# soap-disp-mega-16.net
KiCad netlist of a schematic drawn in EasyEDA
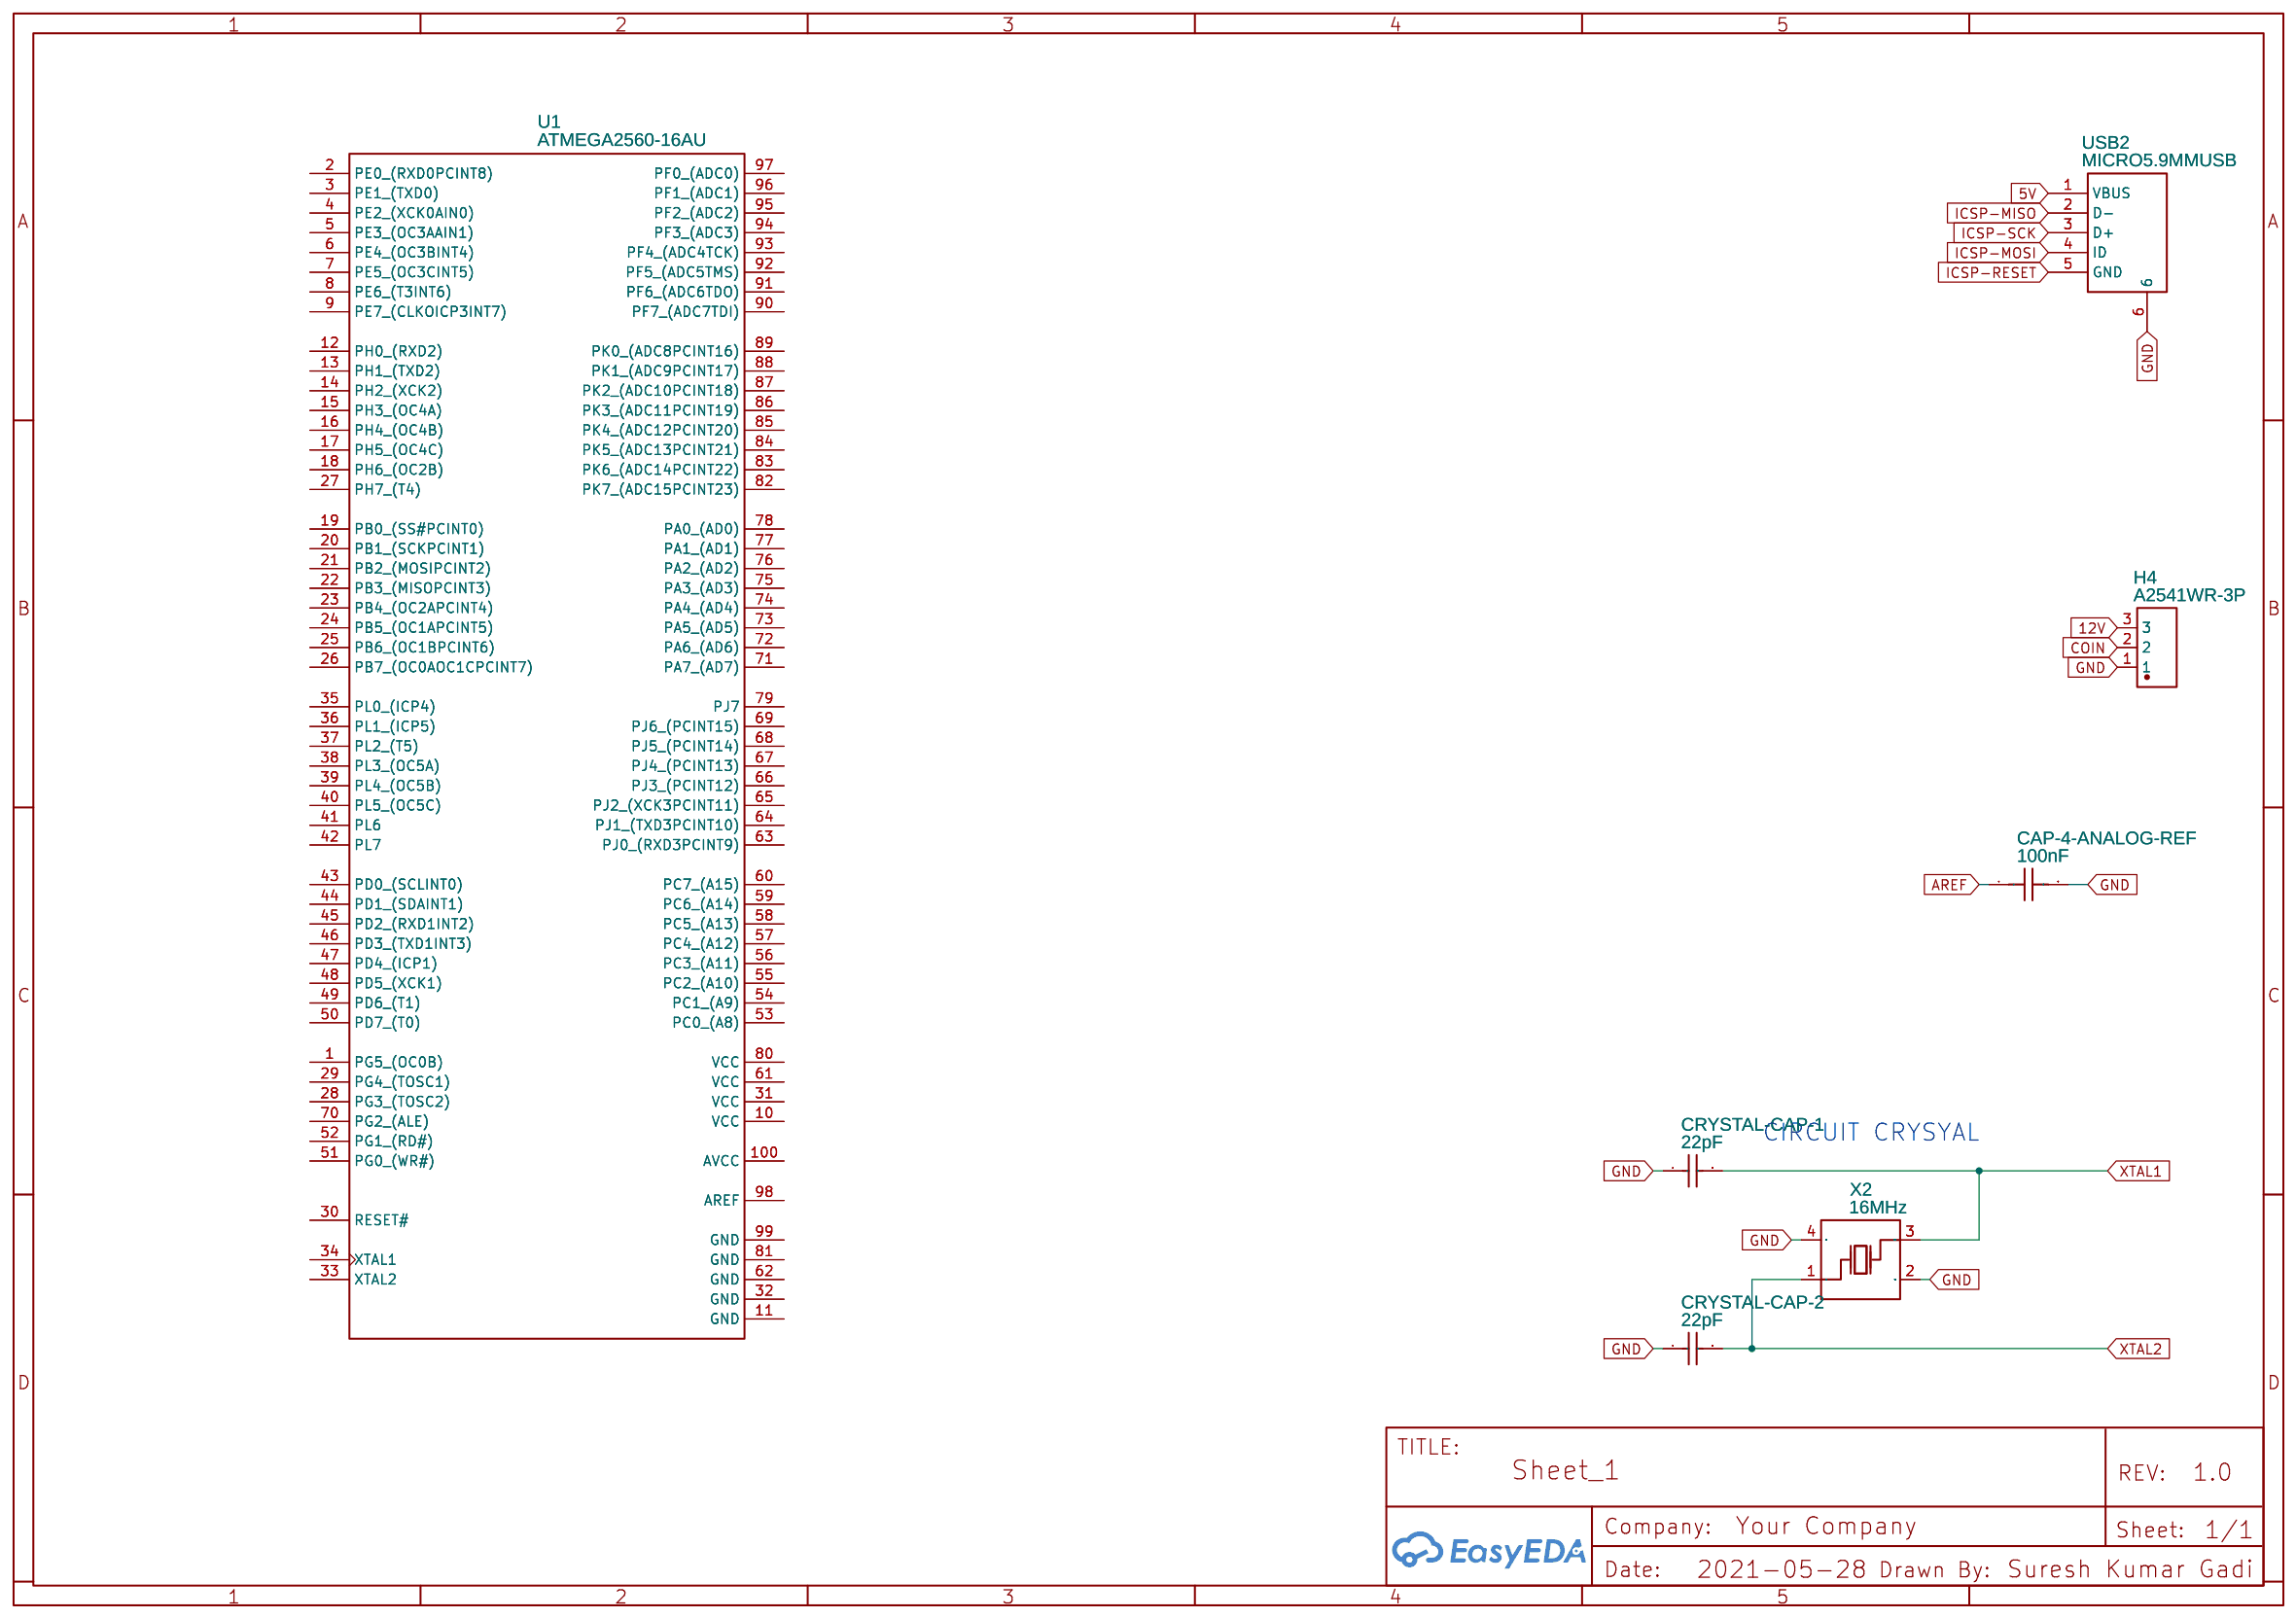
[diagram p0: Computer]
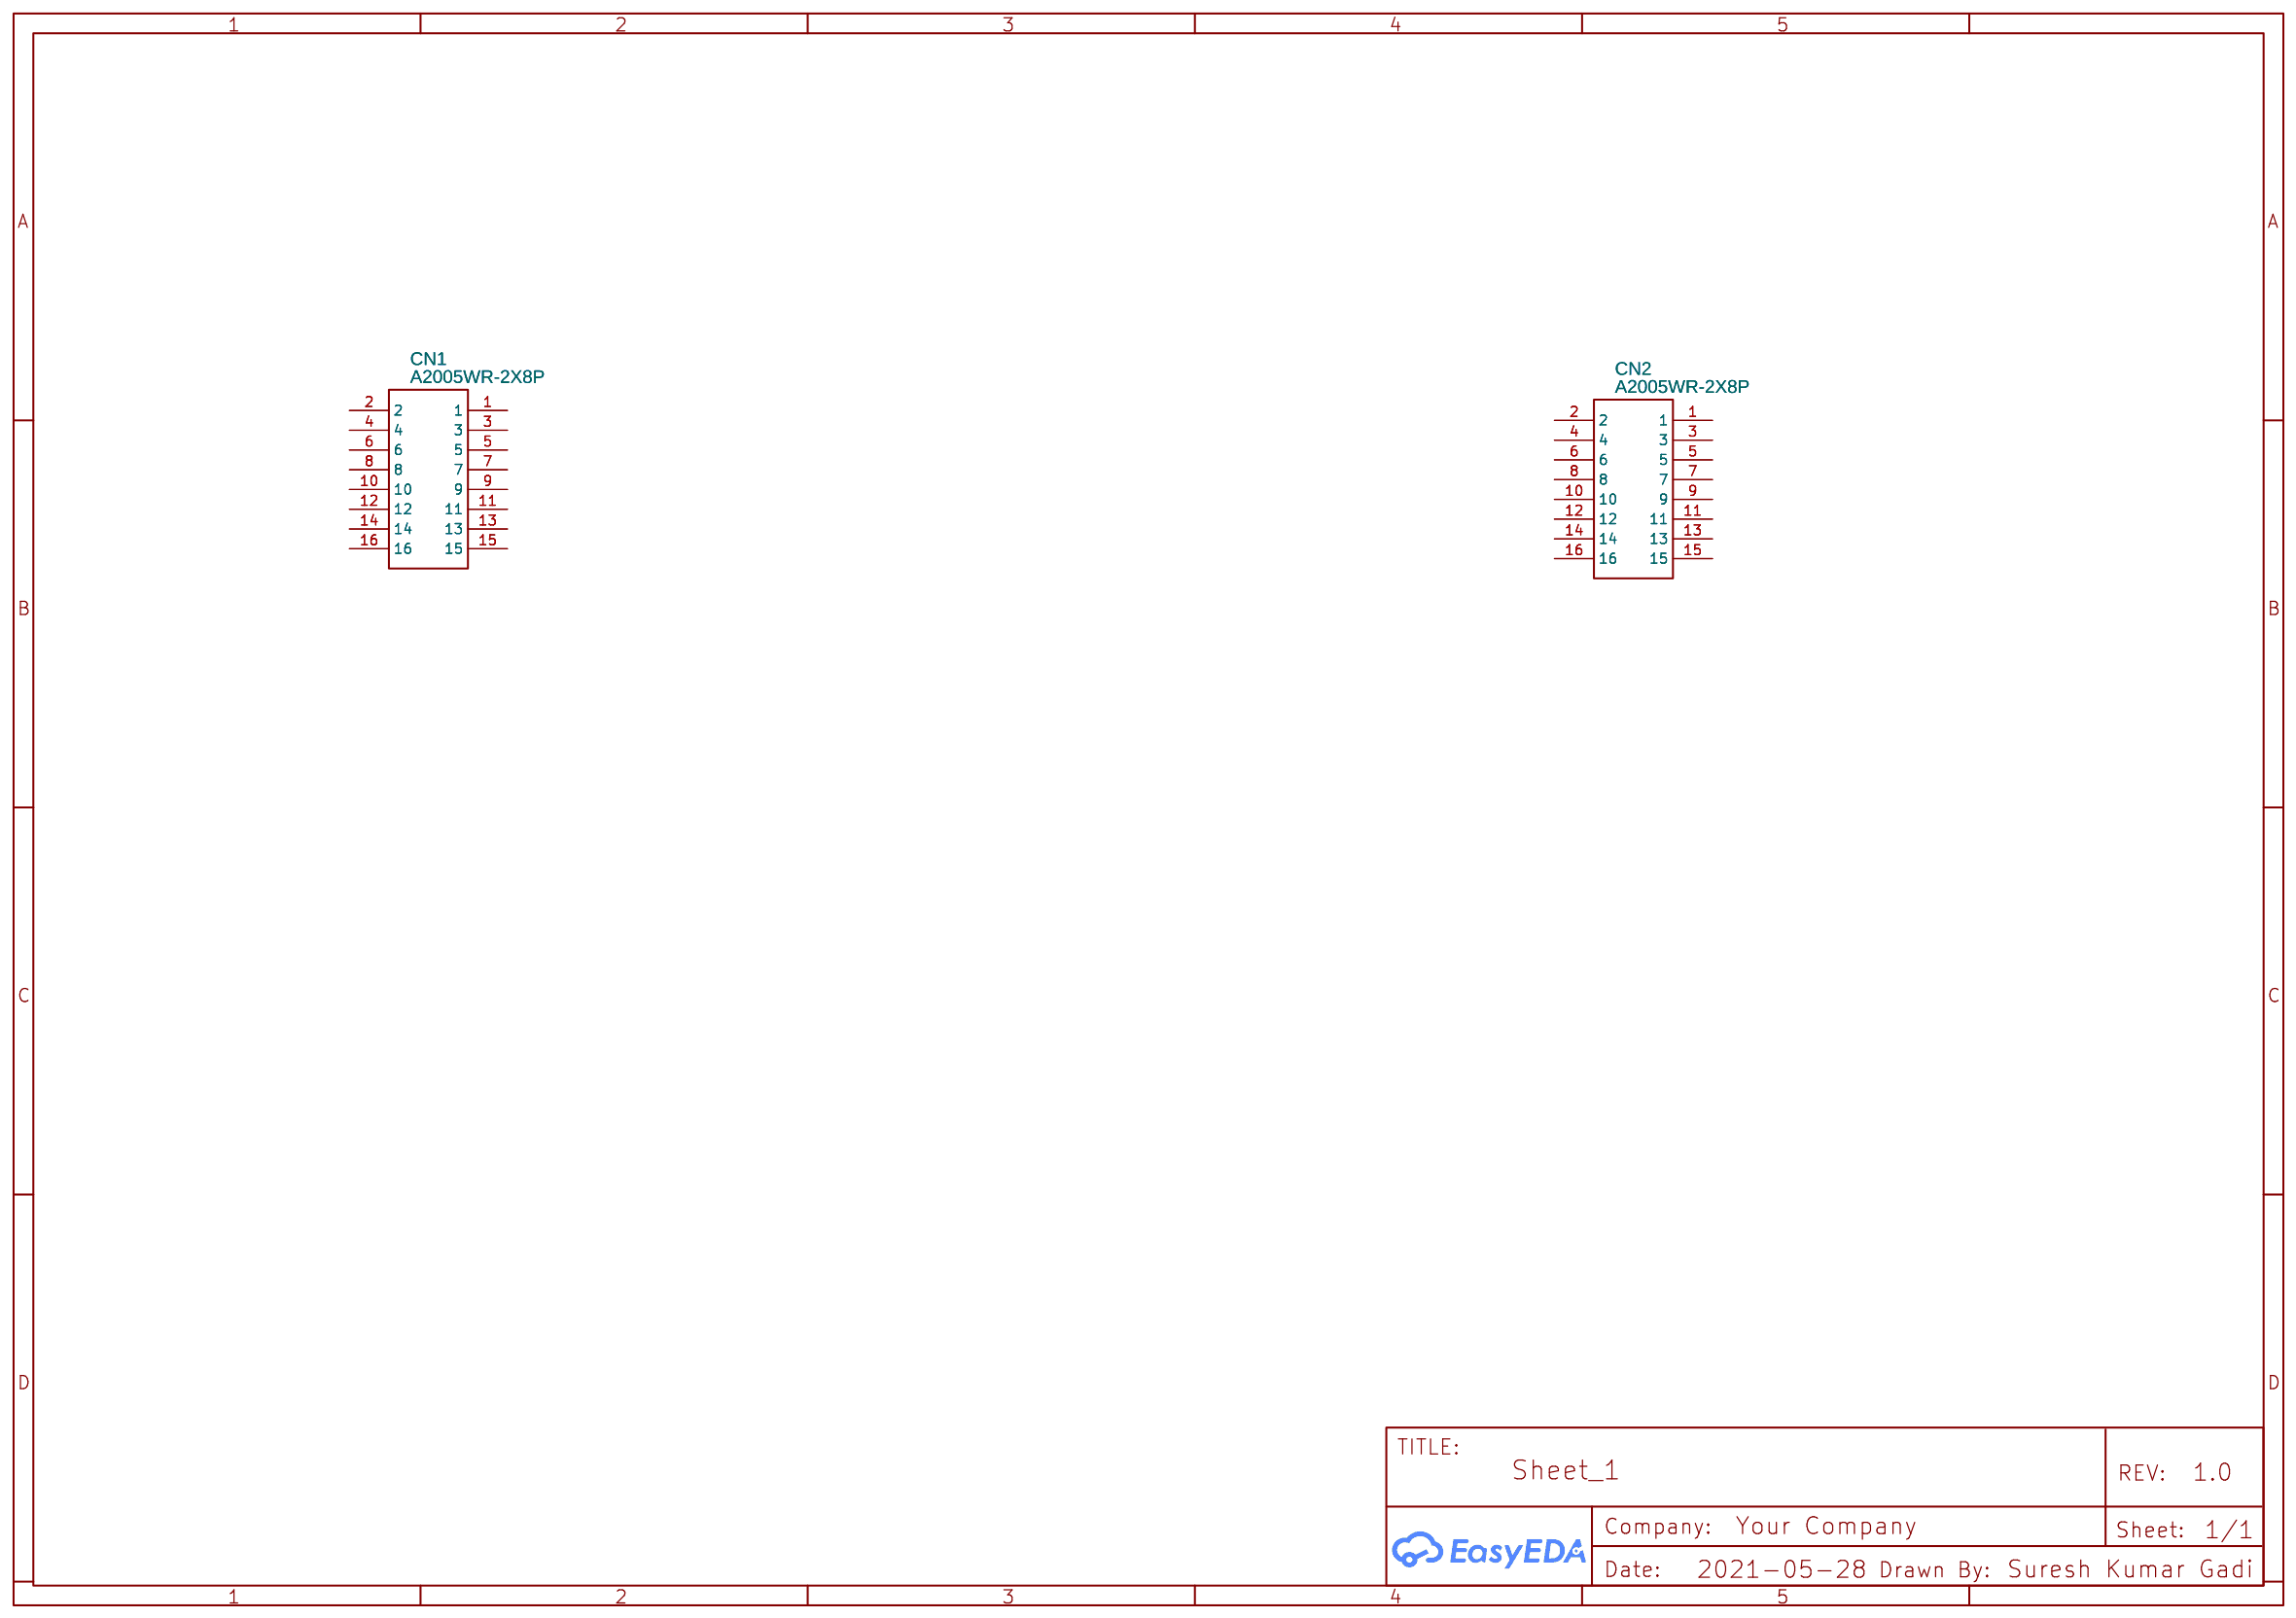
[diagram p1: Connectors]
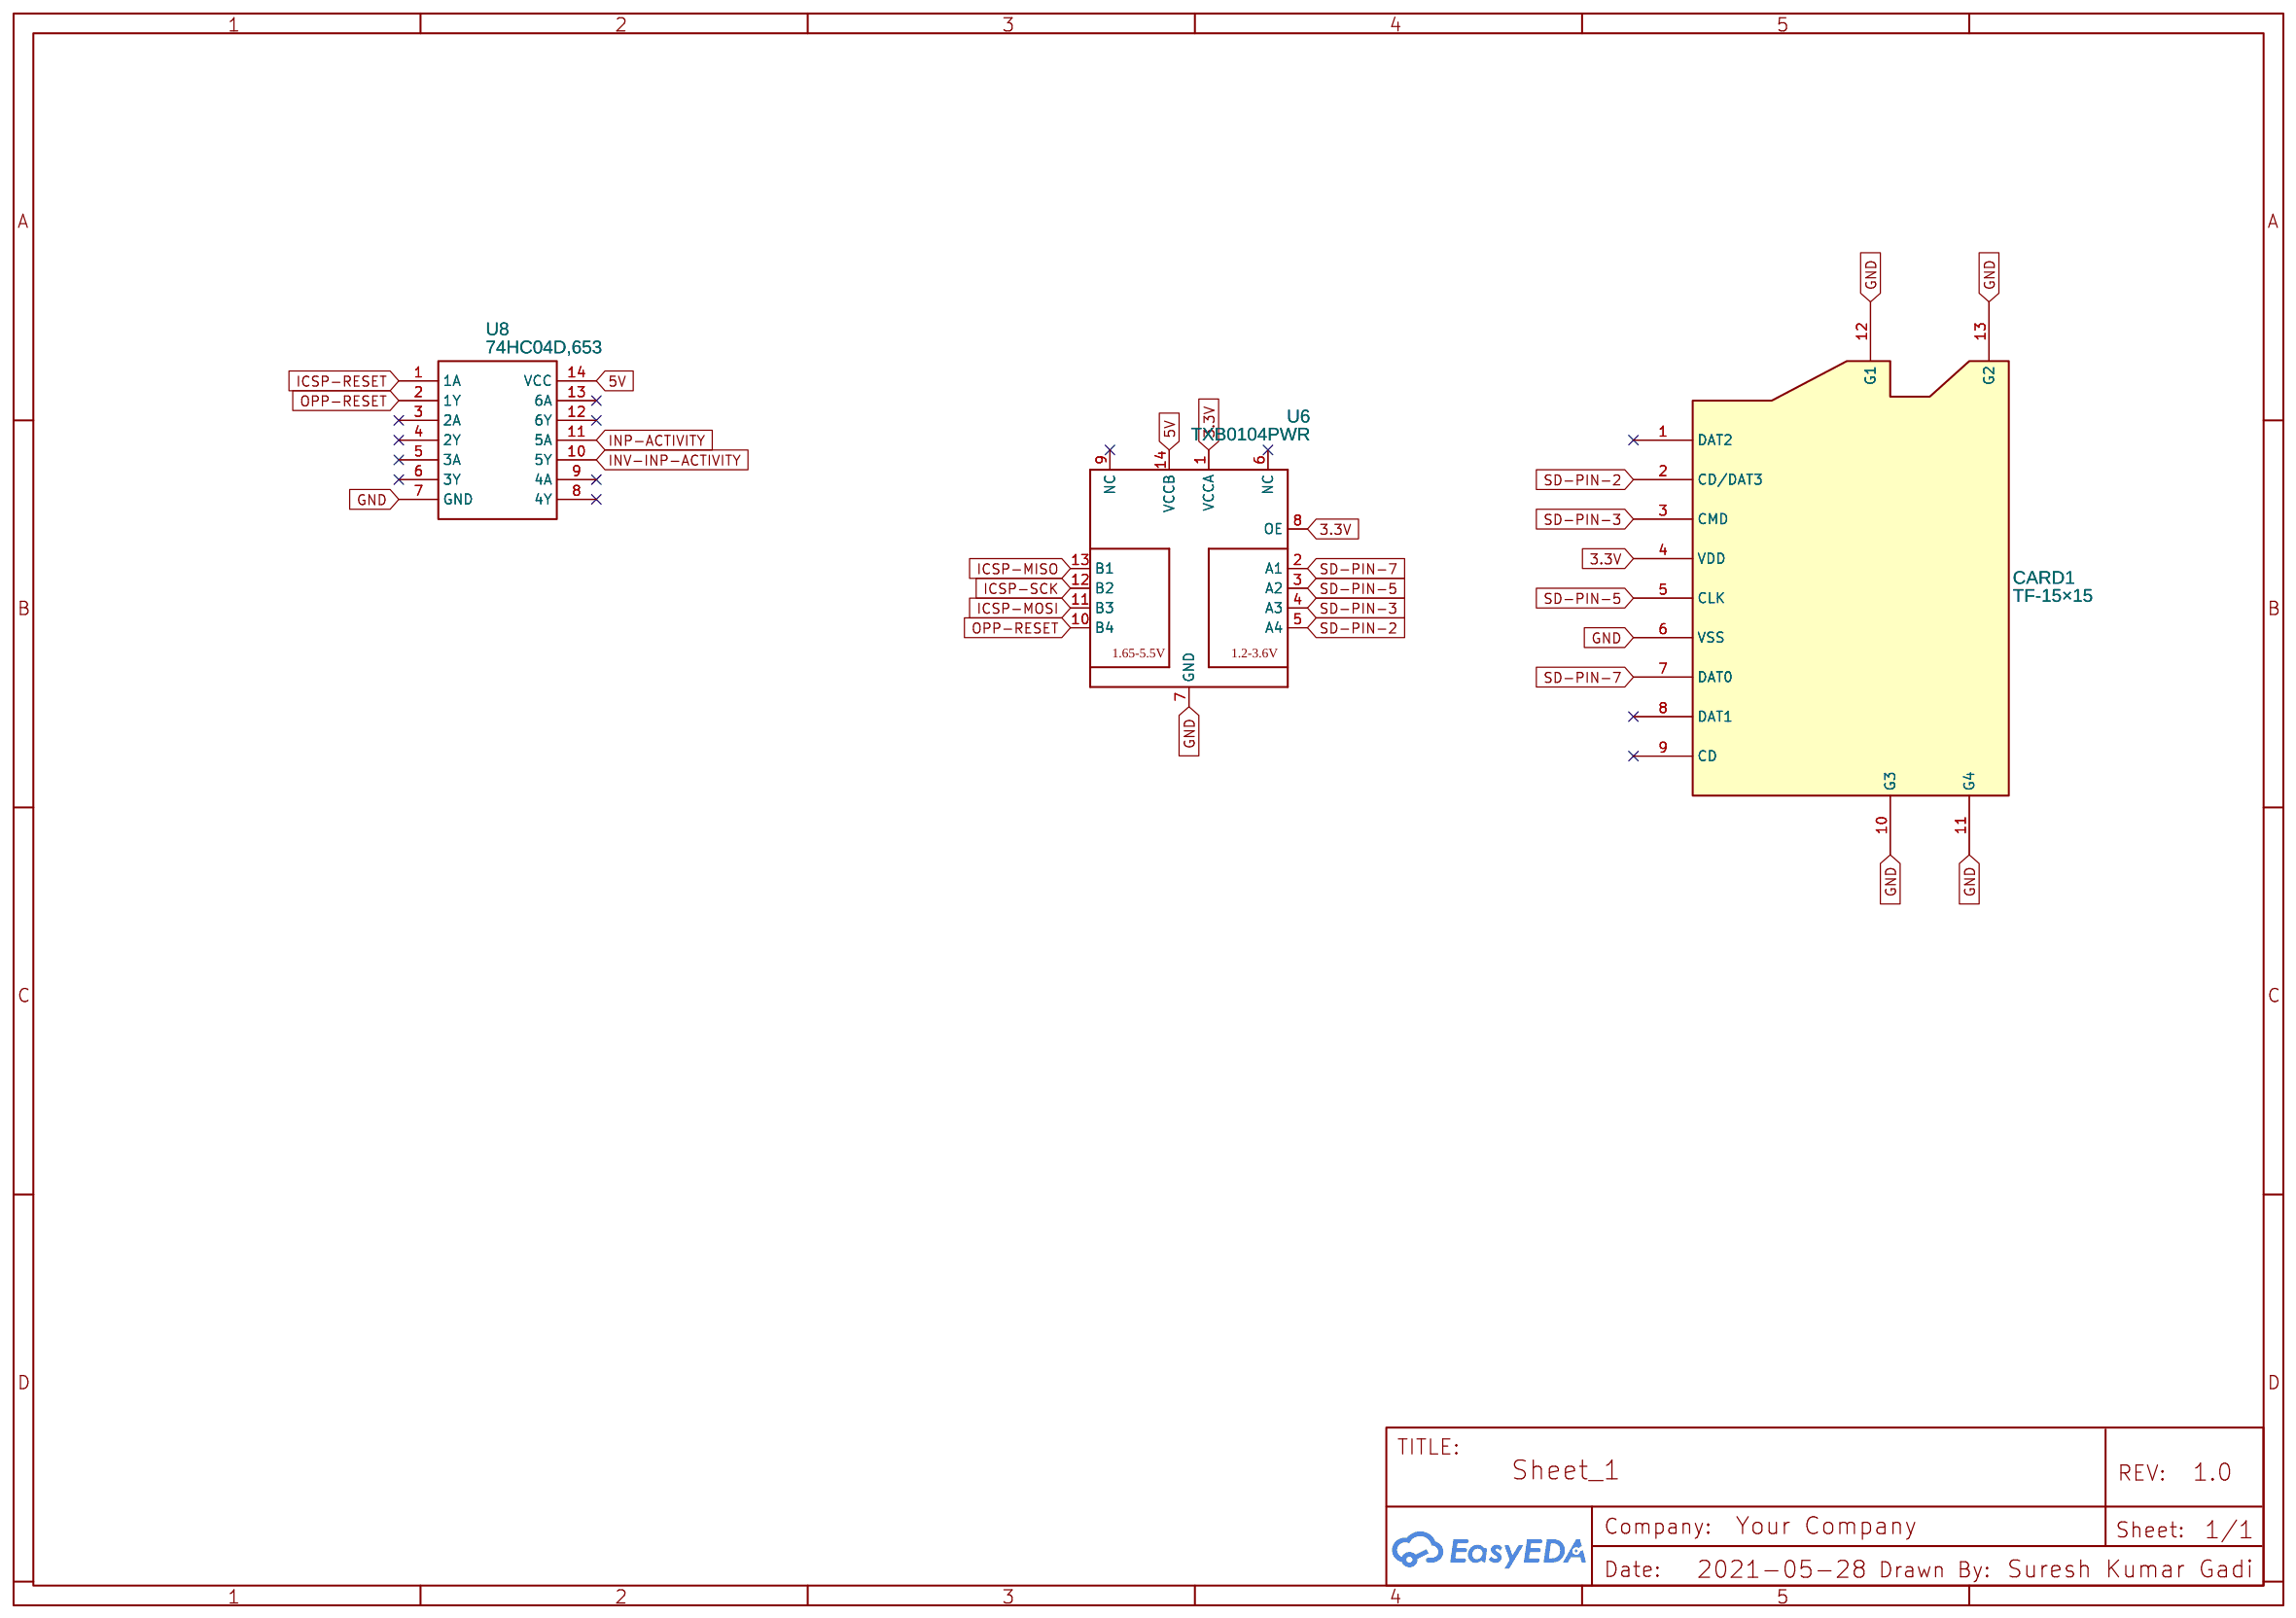
[diagram p2: SD]
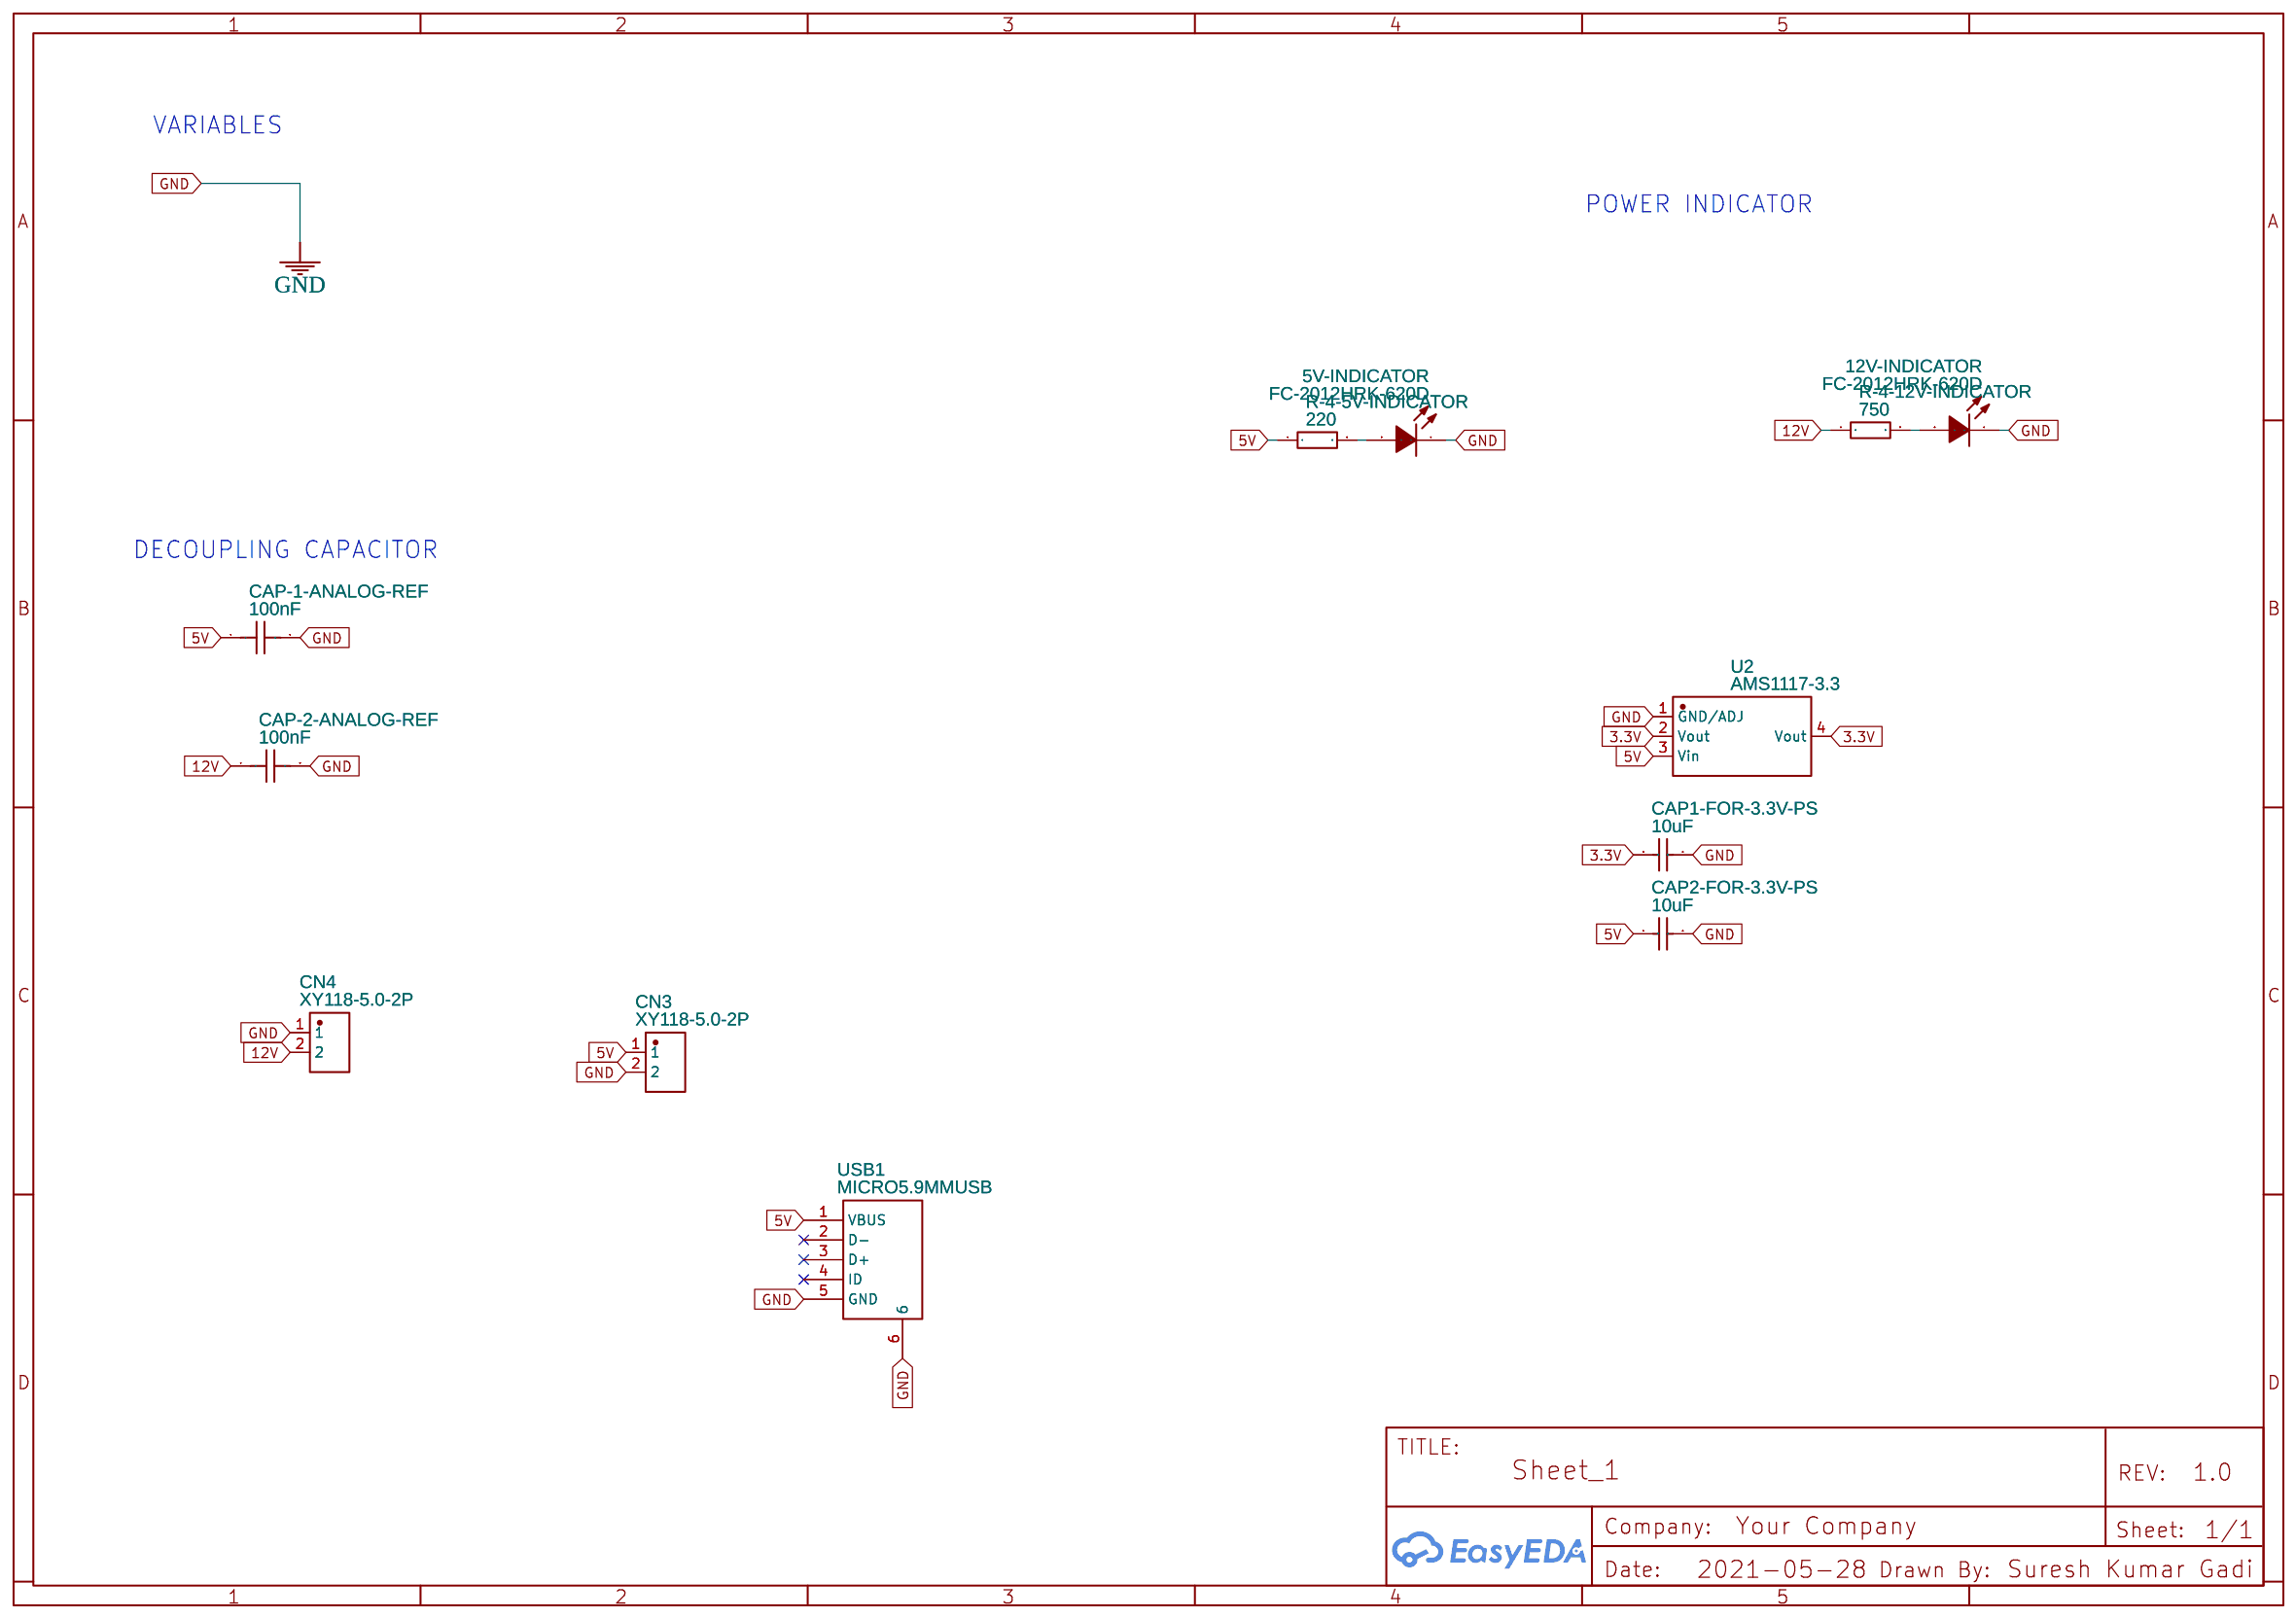
[diagram p3: Power]
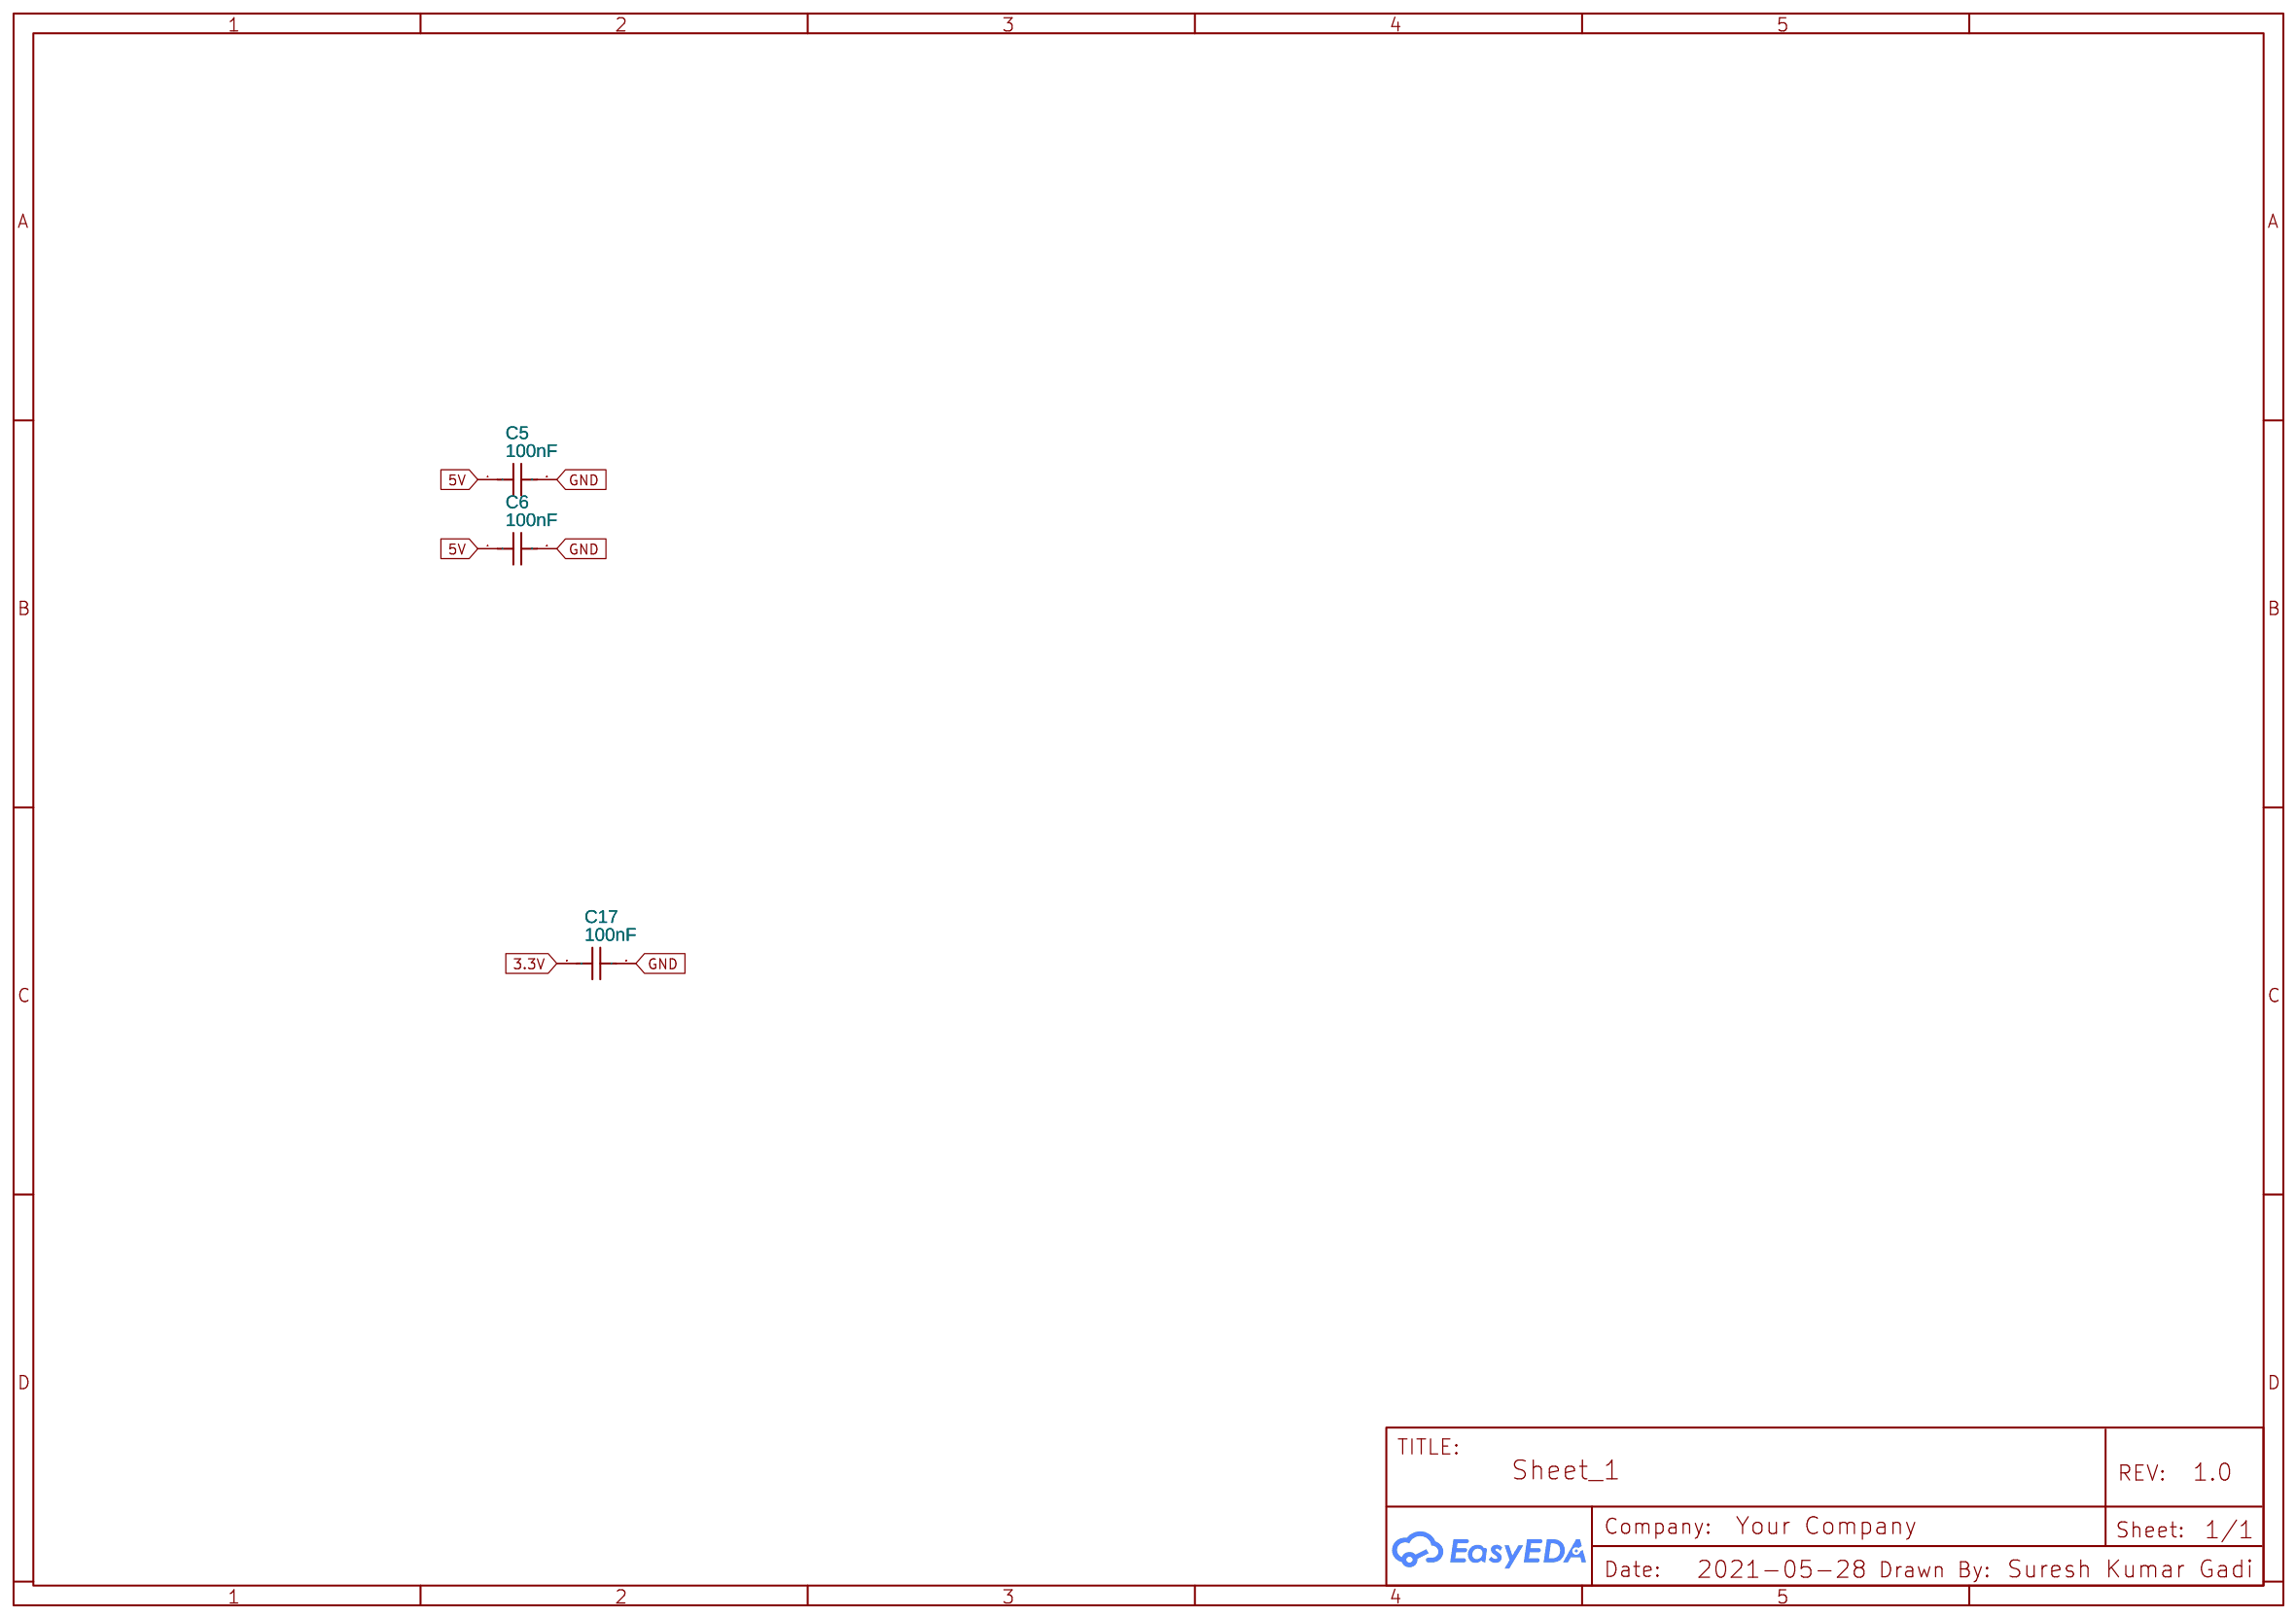
[diagram p4: Capacitors]
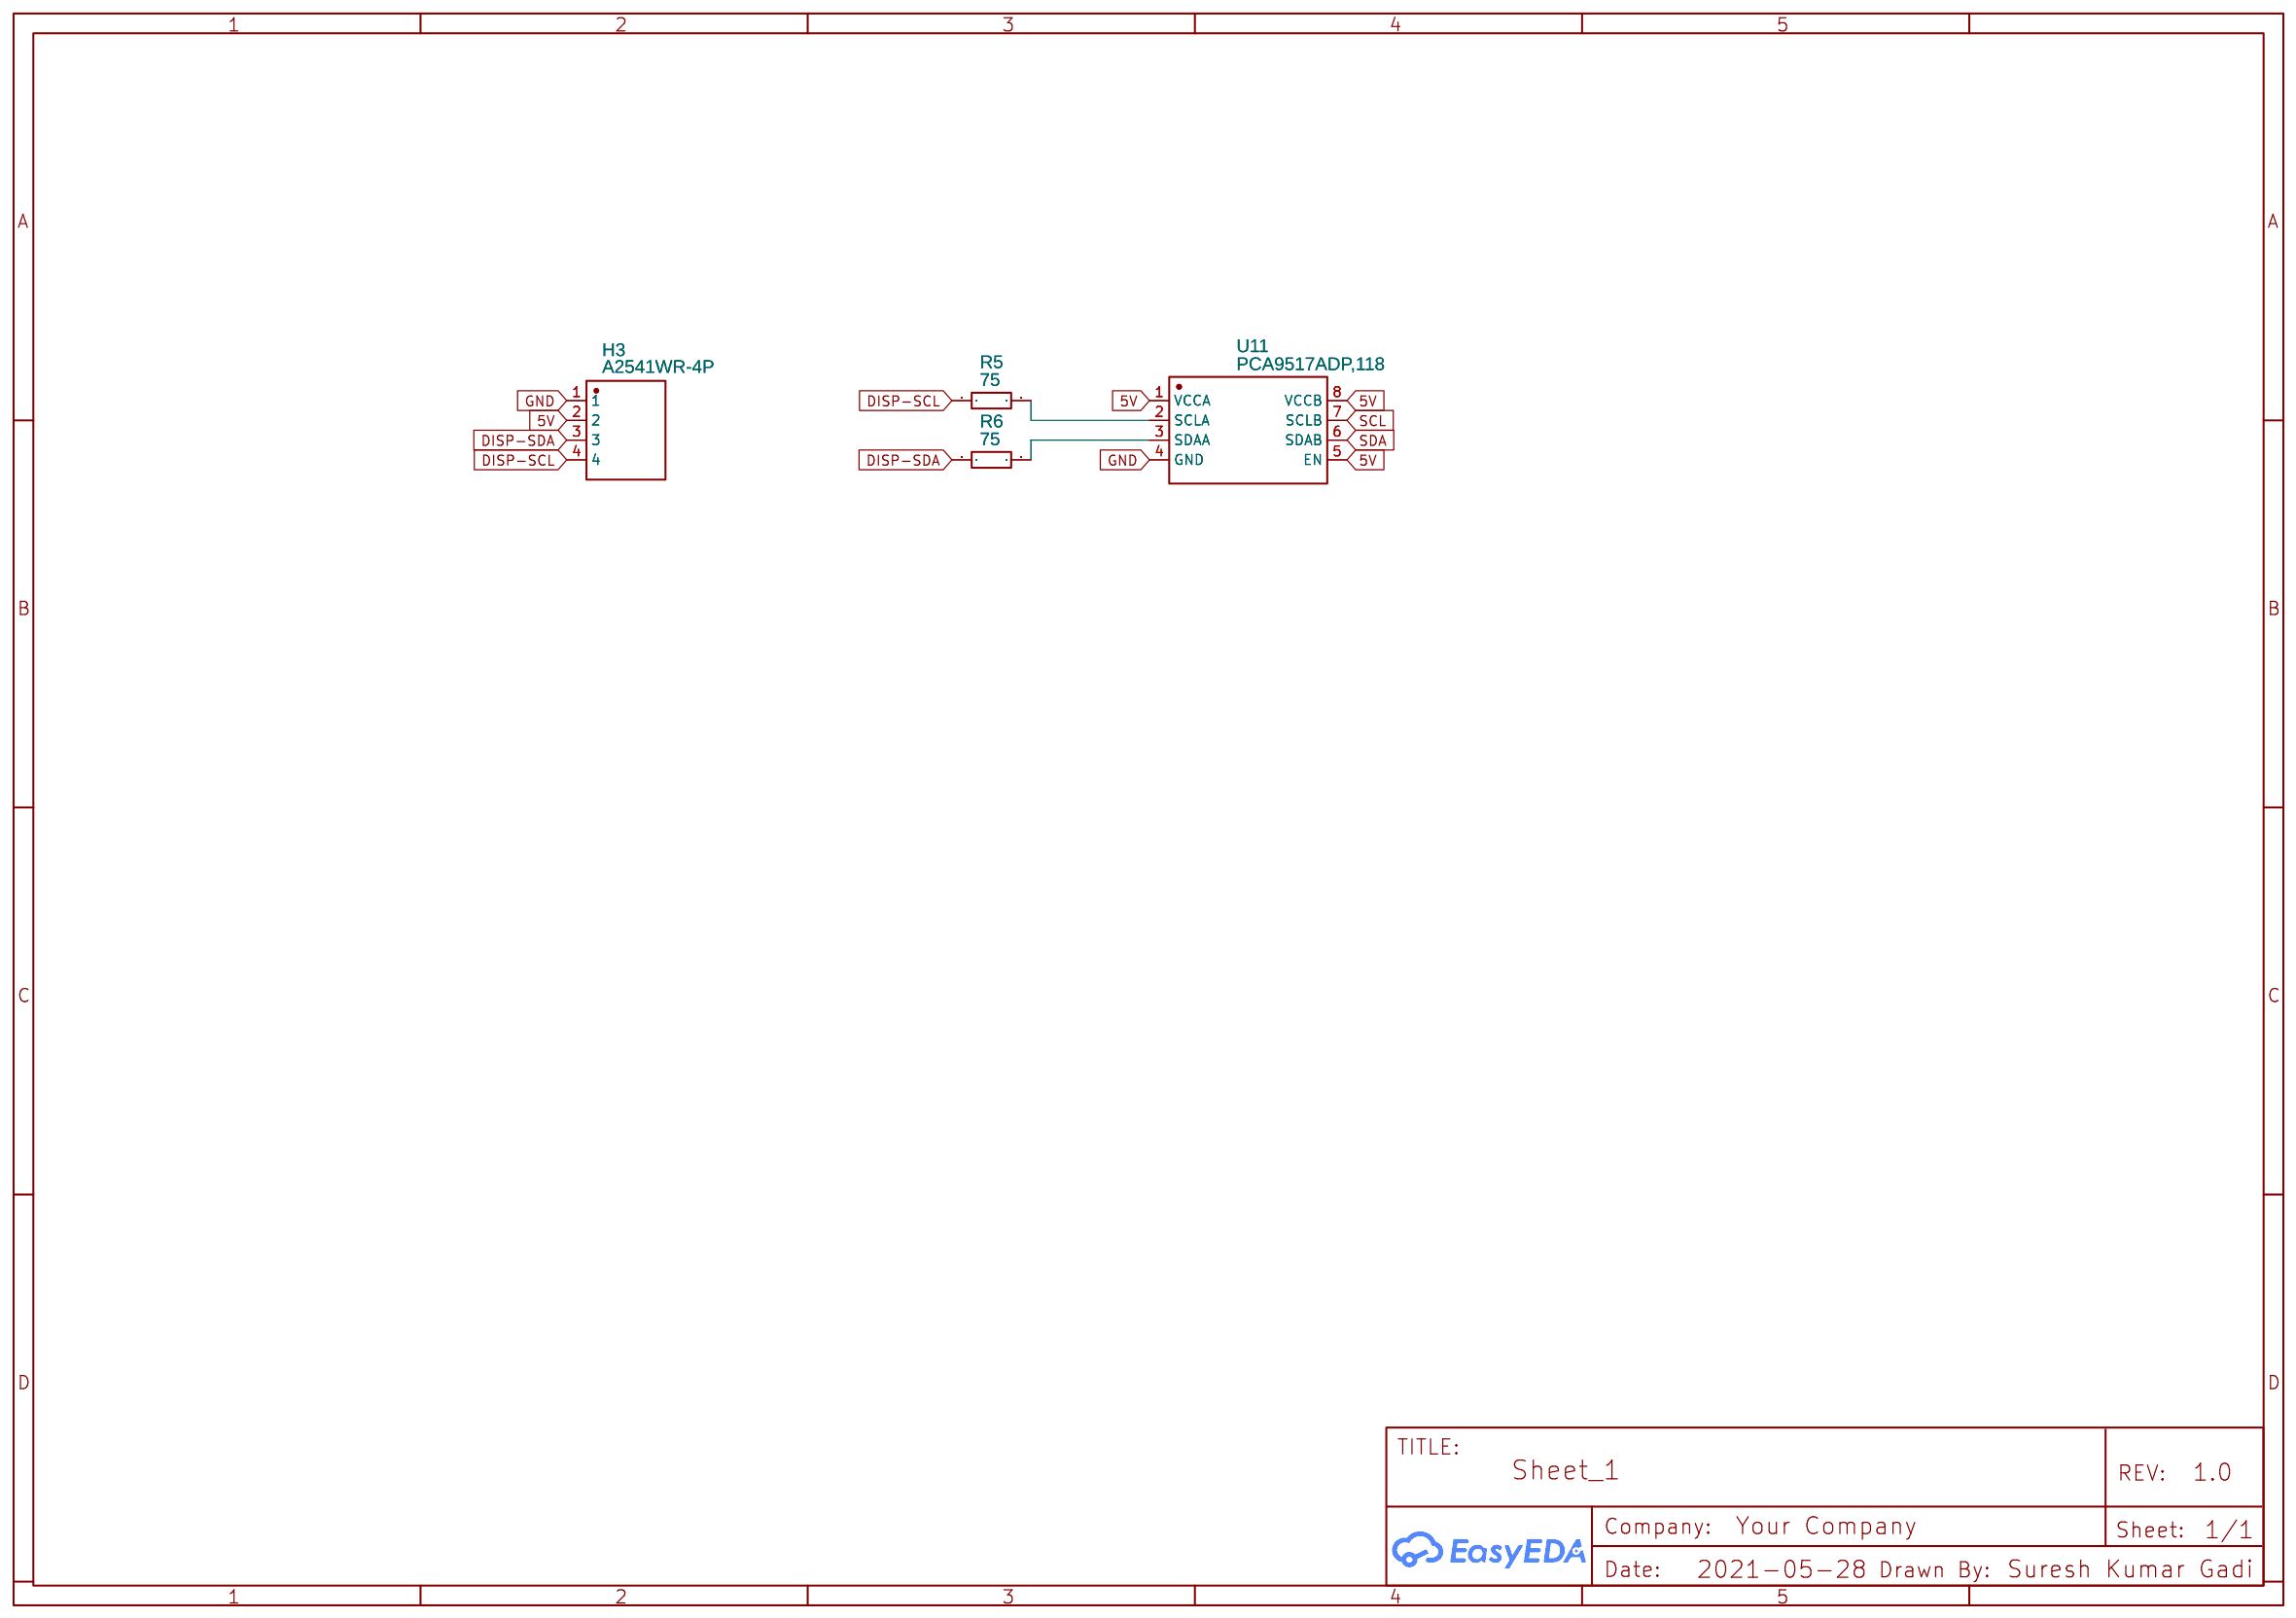
[diagram p5: Display]
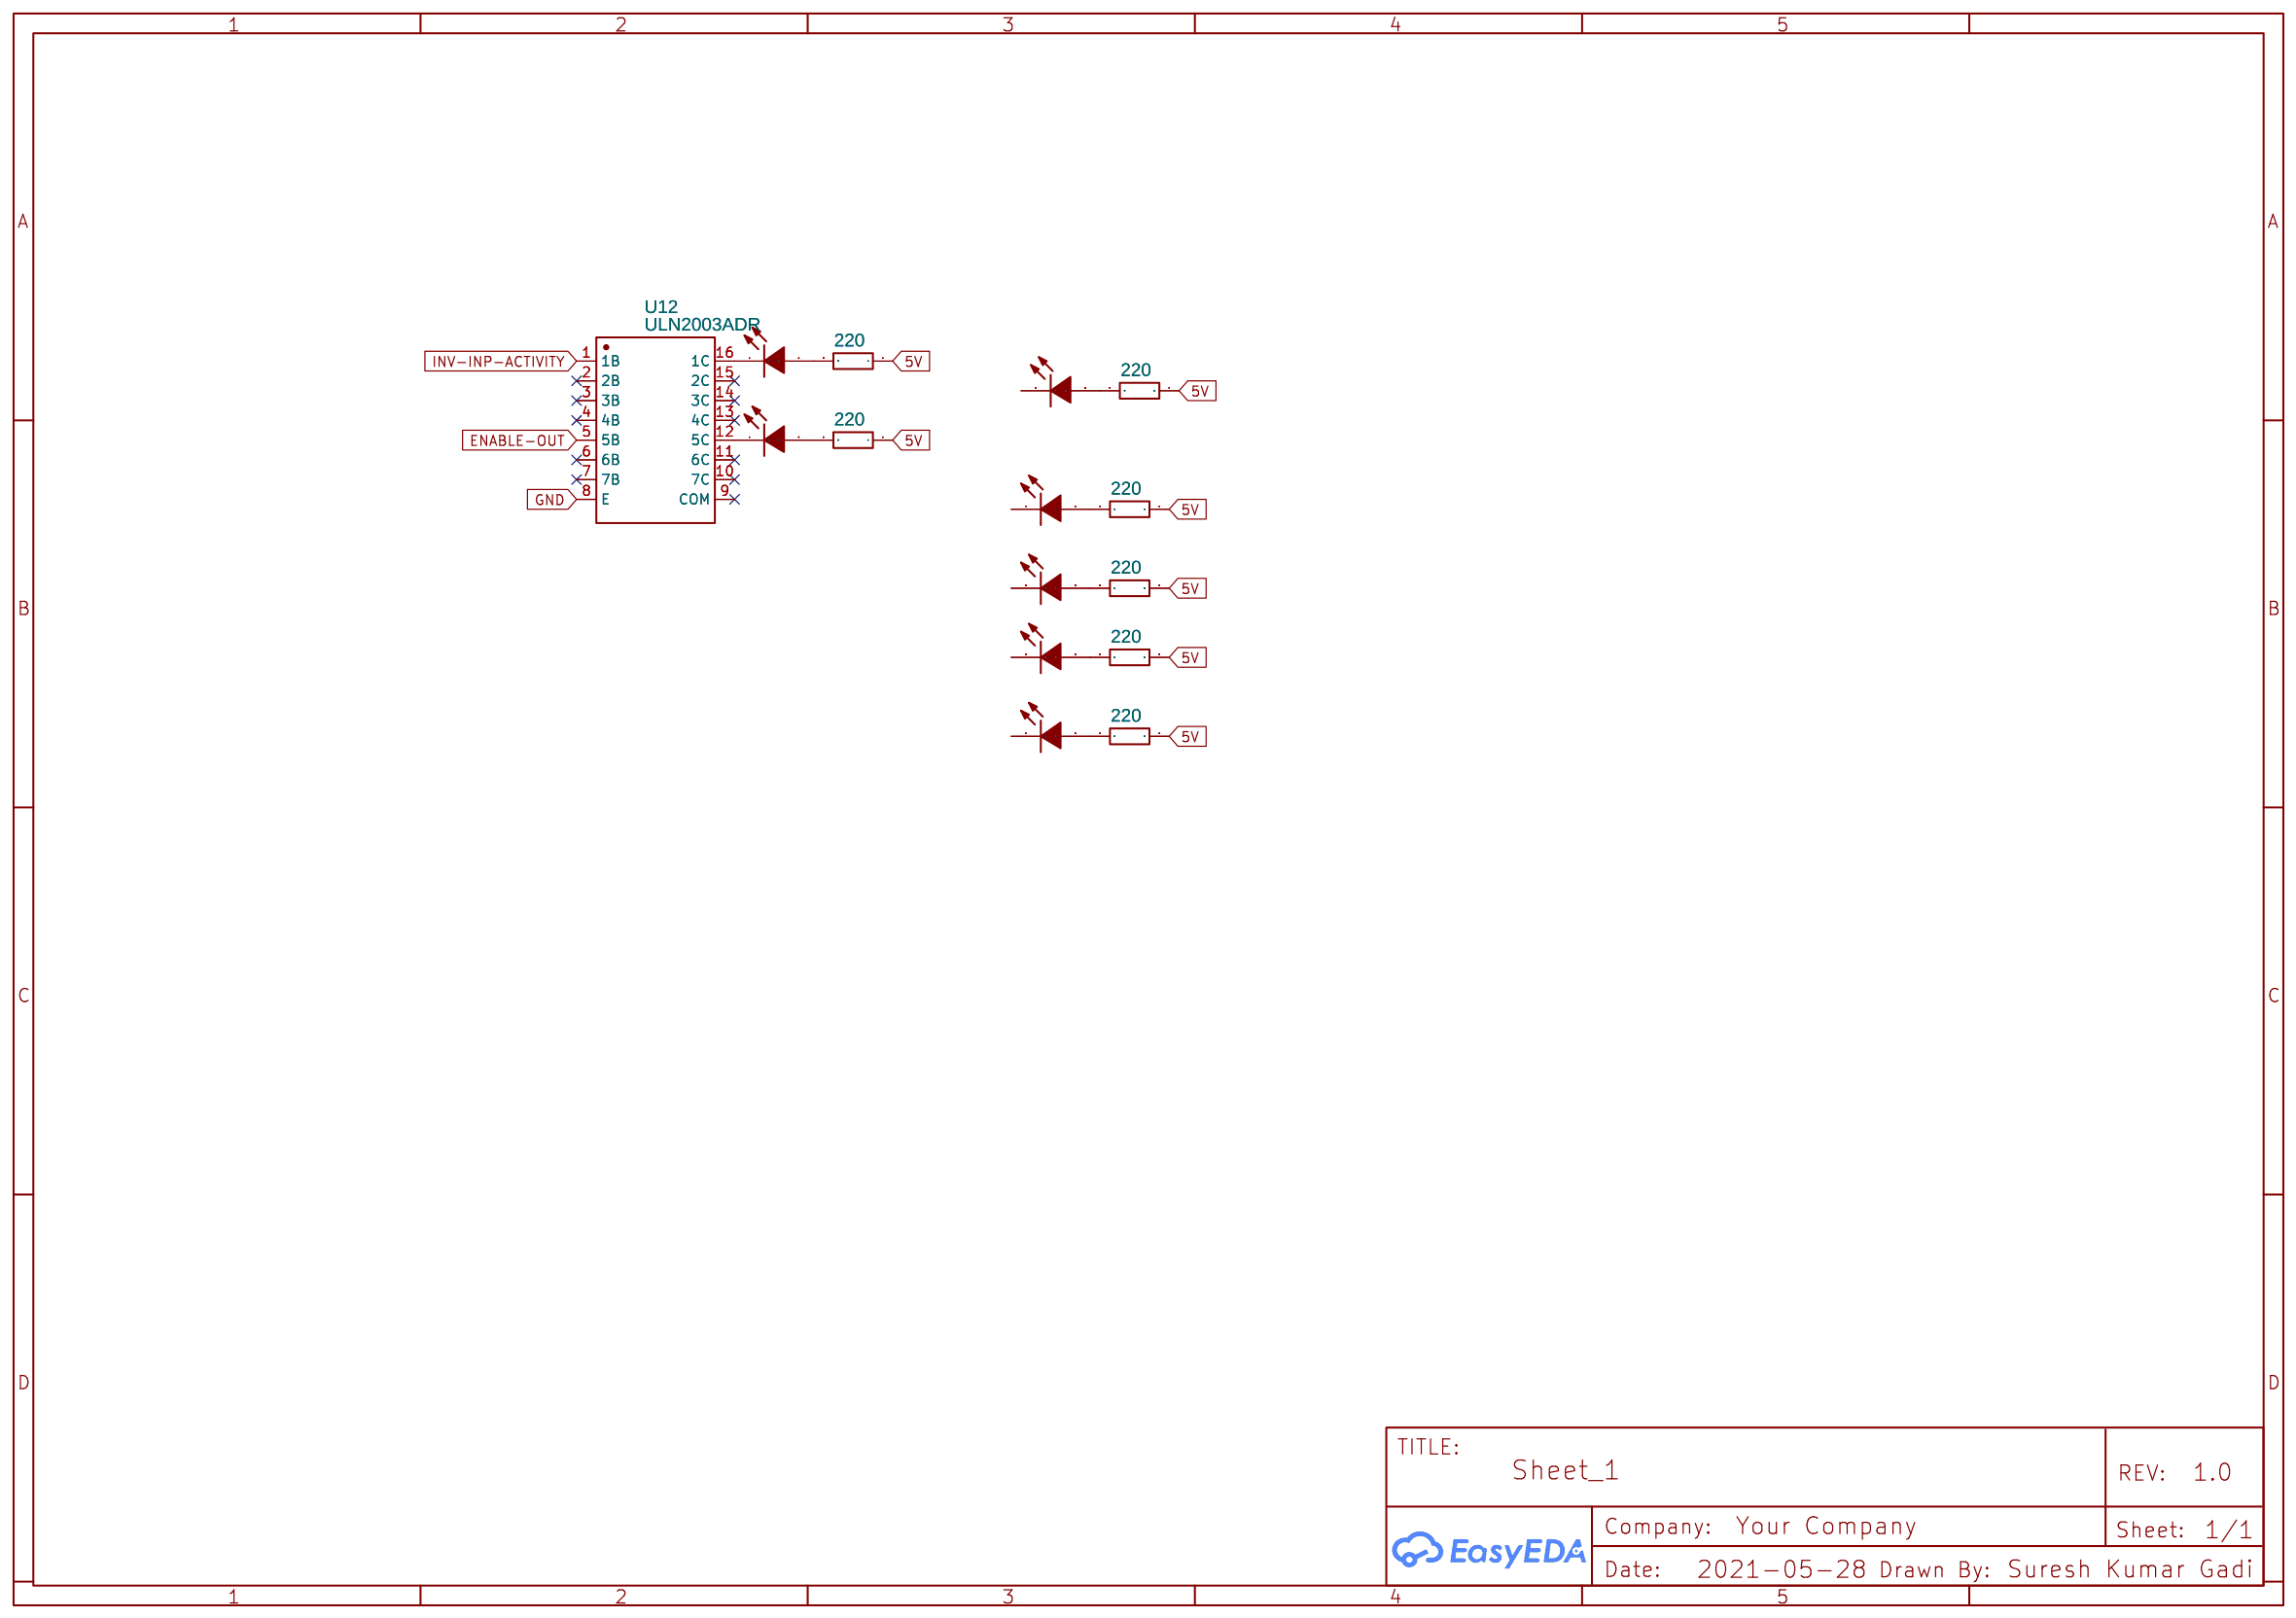
[diagram p6: LEDs]

(export (version "E")
  (design (tool "Eeschema 10.0.6"))
  (components
    (comp (ref "CAP-4-ANALOG-REF")
      (value "100nF")
      (fields
        (field (name "BOM_Manufacturer Part") "CC0603KRX7R9BB104")
        (field (name "BOM_Supplier Part") "C14663")
      )
      (libsource (lib "") (part "CC0603KRX7R9BB104"))
    )
    (comp (ref "CRYSTAL-CAP-1")
      (value "22pF")
      (fields
        (field (name "BOM_Manufacturer Part") "CL21C220JBANNNC")
        (field (name "BOM_Supplier Part") "C1804")
      )
      (libsource (lib "") (part "CL21C220JBANNNC"))
    )
    (comp (ref "CRYSTAL-CAP-2")
      (value "22pF")
      (fields
        (field (name "BOM_Manufacturer Part") "CL21C220JBANNNC")
        (field (name "BOM_Supplier Part") "C1804")
      )
      (libsource (lib "") (part "CL21C220JBANNNC"))
    )
    (comp (ref "H4")
      (value "A2541WR-3P")
      (fields (field (name "BOM_Supplier Part") "C225489"))
      (libsource (lib "") (part "A2541WR-3P"))
    )
    (comp (ref "U1")
      (value "ATMEGA2560-16AU")
      (fields (field (name "BOM_Supplier Part") "C22460"))
      (libsource (lib "") (part "ATMEGA2560-16AU"))
    )
    (comp (ref "USB2")
      (value "MICRO5.9MMUSB")
      (fields
        (field (name "BOM_Manufacturer Part") "MICRO5.9mmusb")
        (field (name "BOM_Supplier Part") "C393940")
      )
      (libsource (lib "") (part "MICRO5.9MMUSB"))
    )
    (comp (ref "X2")
      (value "16MHz")
      (fields
        (field (name "BOM_Manufacturer Part") "X322516MLB4SI")
        (field (name "BOM_Supplier Part") "C13738")
      )
      (libsource (lib "") (part "X322516MLB4SI"))
    )
    (comp (ref "CN1")
      (value "A2005WR-2X8P")
      (fields
        (field (name "BOM_Manufacturer Part") "A2005WR-2x8P")
        (field (name "BOM_Supplier Part") "C225300")
      )
      (libsource (lib "") (part "A2005WR-2X8P"))
    )
    (comp (ref "CN2")
      (value "A2005WR-2X8P")
      (fields
        (field (name "BOM_Manufacturer Part") "A2005WR-2x8P")
        (field (name "BOM_Supplier Part") "C225300")
      )
      (libsource (lib "") (part "A2005WR-2X8P"))
    )
    (comp (ref "CARD1")
      (value "TF-15×15")
      (fields (field (name "BOM_Supplier Part") "C111196"))
      (libsource (lib "") (part "TF-15×15"))
    )
    (comp (ref "U6")
      (value "TXB0104PWR")
      (fields (field (name "BOM_Supplier Part") "C60708"))
      (libsource (lib "") (part "TXB0104PWR"))
    )
    (comp (ref "U8")
      (value "74HC04D,653")
      (fields (field (name "BOM_Supplier Part") "C5590"))
      (libsource (lib "") (part "74HC04D,653"))
    )
    (comp (ref "5V-INDICATOR")
      (value "FC-2012HRK-620D")
      (fields (field (name "BOM_Supplier Part") "C84256"))
      (libsource (lib "") (part "FC-2012HRK-620D_1"))
    )
    (comp (ref "12V-INDICATOR")
      (value "FC-2012HRK-620D")
      (fields (field (name "BOM_Supplier Part") "C84256"))
      (libsource (lib "") (part "FC-2012HRK-620D"))
    )
    (comp (ref "CAP-1-ANALOG-REF")
      (value "100nF")
      (fields
        (field (name "BOM_Manufacturer Part") "CC0603KRX7R9BB104")
        (field (name "BOM_Supplier Part") "C14663")
      )
      (libsource (lib "") (part "CC0603KRX7R9BB104_1"))
    )
    (comp (ref "CAP-2-ANALOG-REF")
      (value "100nF")
      (fields
        (field (name "BOM_Manufacturer Part") "CC0603KRX7R9BB104")
        (field (name "BOM_Supplier Part") "C14663")
      )
      (libsource (lib "") (part "CC0603KRX7R9BB104"))
    )
    (comp (ref "CAP1-FOR-3.3V-PS")
      (value "10uF")
      (fields
        (field (name "BOM_Manufacturer Part") "CL21A106KAYNNNE")
        (field (name "BOM_Supplier Part") "C15850")
      )
      (libsource (lib "") (part "CL21A106KAYNNNE_1"))
    )
    (comp (ref "CAP2-FOR-3.3V-PS")
      (value "10uF")
      (fields
        (field (name "BOM_Manufacturer Part") "CL21A106KAYNNNE")
        (field (name "BOM_Supplier Part") "C15850")
      )
      (libsource (lib "") (part "CL21A106KAYNNNE"))
    )
    (comp (ref "CN3")
      (value "XY118-5.0-2P")
      (fields (field (name "BOM_Supplier Part") "C784922"))
      (libsource (lib "") (part "XY118-5.0-2P"))
    )
    (comp (ref "CN4")
      (value "XY118-5.0-2P")
      (fields (field (name "BOM_Supplier Part") "C784922"))
      (libsource (lib "") (part "XY118-5.0-2P"))
    )
    (comp (ref "R-4-5V-INDICATOR")
      (value "220")
      (fields
        (field (name "BOM_Manufacturer Part") "0805W8F2200T5E")
        (field (name "BOM_Supplier Part") "C17557")
      )
      (libsource (lib "") (part "0805W8F2200T5E"))
    )
    (comp (ref "R-4-12V-INDICATOR")
      (value "750")
      (fields
        (field (name "BOM_Manufacturer Part") "1206W4F7500T5E")
        (field (name "BOM_Supplier Part") "C17985")
      )
      (libsource (lib "") (part "1206W4F7500T5E"))
    )
    (comp (ref "U2")
      (value "AMS1117-3.3")
      (fields (field (name "BOM_Supplier Part") "C6186"))
      (libsource (lib "") (part "AMS1117-3.3"))
    )
    (comp (ref "USB1")
      (value "MICRO5.9MMUSB")
      (fields
        (field (name "BOM_Manufacturer Part") "MICRO5.9mmusb")
        (field (name "BOM_Supplier Part") "C393940")
      )
      (libsource (lib "") (part "MICRO5.9MMUSB"))
    )
    (comp (ref "C5")
      (value "100nF")
      (fields
        (field (name "BOM_Manufacturer Part") "CC0603KRX7R9BB104")
        (field (name "BOM_Supplier Part") "C14663")
      )
      (libsource (lib "") (part "CC0603KRX7R9BB104"))
    )
    (comp (ref "C6")
      (value "100nF")
      (fields
        (field (name "BOM_Manufacturer Part") "CC0603KRX7R9BB104")
        (field (name "BOM_Supplier Part") "C14663")
      )
      (libsource (lib "") (part "CC0603KRX7R9BB104"))
    )
    (comp (ref "C17")
      (value "100nF")
      (fields
        (field (name "BOM_Manufacturer Part") "CC0603KRX7R9BB104")
        (field (name "BOM_Supplier Part") "C14663")
      )
      (libsource (lib "") (part "CC0603KRX7R9BB104"))
    )
    (comp (ref "H3")
      (value "A2541WR-4P")
      (fields (field (name "BOM_Supplier Part") "C225490"))
      (libsource (lib "") (part "A2541WR-4P"))
    )
    (comp (ref "R5")
      (value "75")
      (fields
        (field (name "BOM_Manufacturer Part") "0402WGF750JTCE")
        (field (name "BOM_Supplier Part") "C25133")
      )
      (libsource (lib "") (part "0402WGF750JTCE"))
    )
    (comp (ref "R6")
      (value "75")
      (fields
        (field (name "BOM_Manufacturer Part") "0402WGF750JTCE")
        (field (name "BOM_Supplier Part") "C25133")
      )
      (libsource (lib "") (part "0402WGF750JTCE"))
    )
    (comp (ref "U11")
      (value "PCA9517ADP,118")
      (fields (field (name "BOM_Supplier Part") "C80799"))
      (libsource (lib "") (part "PCA9517ADP,118"))
    )
    (comp (ref "ENAMEOUTINDICATOR1")
      (value "FC-2012HRK-620D")
      (fields (field (name "BOM_Supplier Part") "C84256"))
      (libsource (lib "") (part "FC-2012HRK-620D_1"))
    )
    (comp (ref "ENAMEOUTINDICATOR2")
      (value "FC-2012HRK-620D")
      (fields (field (name "BOM_Supplier Part") "C84256"))
      (libsource (lib "") (part "FC-2012HRK-620D_1"))
    )
    (comp (ref "ENAMEOUTINDICATOR3")
      (value "FC-2012HRK-620D")
      (fields (field (name "BOM_Supplier Part") "C84256"))
      (libsource (lib "") (part "FC-2012HRK-620D_1"))
    )
    (comp (ref "ENAMEOUTINDICATOR4")
      (value "FC-2012HRK-620D")
      (fields (field (name "BOM_Supplier Part") "C84256"))
      (libsource (lib "") (part "FC-2012HRK-620D_1"))
    )
    (comp (ref "INPUTACTIVITYINDICATOR1")
      (value "FC-2012HRK-620D")
      (fields (field (name "BOM_Supplier Part") "C84256"))
      (libsource (lib "") (part "FC-2012HRK-620D"))
    )
    (comp (ref "INPUTACTIVITYINDICATOR2")
      (value "FC-2012HRK-620D")
      (fields (field (name "BOM_Supplier Part") "C84256"))
      (libsource (lib "") (part "FC-2012HRK-620D"))
    )
    (comp (ref "INPUTACTIVITYINDICATOR3")
      (value "FC-2012HRK-620D")
      (fields (field (name "BOM_Supplier Part") "C84256"))
      (libsource (lib "") (part "FC-2012HRK-620D"))
    )
    (comp (ref "R-4-1V-INDICATOR")
      (value "220")
      (fields
        (field (name "BOM_Manufacturer Part") "0805W8F2200T5E")
        (field (name "BOM_Supplier Part") "C17557")
      )
      (libsource (lib "") (part "0805W8F2200T5E"))
    )
    (comp (ref "R-4-2V-INDICATOR")
      (value "220")
      (fields
        (field (name "BOM_Manufacturer Part") "0805W8F2200T5E")
        (field (name "BOM_Supplier Part") "C17557")
      )
      (libsource (lib "") (part "0805W8F2200T5E_3"))
    )
    (comp (ref "R-4-3V-INDICATOR")
      (value "220")
      (fields
        (field (name "BOM_Manufacturer Part") "0805W8F2200T5E")
        (field (name "BOM_Supplier Part") "C17557")
      )
      (libsource (lib "") (part "0805W8F2200T5E_2"))
    )
    (comp (ref "RESFORENAMEOUTINDICATOR1")
      (value "220")
      (fields
        (field (name "BOM_Manufacturer Part") "0805W8F2200T5E")
        (field (name "BOM_Supplier Part") "C17557")
      )
      (libsource (lib "") (part "0805W8F2200T5E_1"))
    )
    (comp (ref "RESFORENAMEOUTINDICATOR2")
      (value "220")
      (fields
        (field (name "BOM_Manufacturer Part") "0805W8F2200T5E")
        (field (name "BOM_Supplier Part") "C17557")
      )
      (libsource (lib "") (part "0805W8F2200T5E_1"))
    )
    (comp (ref "RESFORENAMEOUTINDICATOR3")
      (value "220")
      (fields
        (field (name "BOM_Manufacturer Part") "0805W8F2200T5E")
        (field (name "BOM_Supplier Part") "C17557")
      )
      (libsource (lib "") (part "0805W8F2200T5E_1"))
    )
    (comp (ref "RESFORENAMEOUTINDICATOR4")
      (value "220")
      (fields
        (field (name "BOM_Manufacturer Part") "0805W8F2200T5E")
        (field (name "BOM_Supplier Part") "C17557")
      )
      (libsource (lib "") (part "0805W8F2200T5E_1"))
    )
    (comp (ref "U12")
      (value "ULN2003ADR")
      (fields (field (name "BOM_Supplier Part") "C7512"))
      (libsource (lib "") (part "ULN2003ADR"))
    )
  )
  (nets
    (net (code "1") (name "3.3V") (class "Default")
      (node (ref "C17") (pin "1") (pinfunction "1_1") (pintype "unspecified"))
      (node (ref "CAP1-FOR-3.3V-PS") (pin "1") (pinfunction "1_1") (pintype "input"))
      (node (ref "CARD1") (pin "4") (pinfunction "VDD_4") (pintype "input"))
      (node (ref "U2") (pin "2") (pinfunction "Vout_2") (pintype "unspecified"))
      (node (ref "U2") (pin "4") (pinfunction "Vout_4") (pintype "unspecified"))
      (node (ref "U6") (pin "1") (pinfunction "VCCA_1") (pintype "unspecified"))
      (node (ref "U6") (pin "8") (pinfunction "OE_8") (pintype "unspecified"))
    )
    (net (code "2") (name "5V") (class "Default")
      (node (ref "C5") (pin "1") (pinfunction "1_1") (pintype "unspecified"))
      (node (ref "C6") (pin "1") (pinfunction "1_1") (pintype "unspecified"))
      (node (ref "CAP-1-ANALOG-REF") (pin "1") (pinfunction "1_1") (pintype "unspecified"))
      (node (ref "CAP2-FOR-3.3V-PS") (pin "1") (pinfunction "1_1") (pintype "input"))
      (node (ref "CN3") (pin "1") (pinfunction "1_1") (pintype "unspecified"))
      (node (ref "H3") (pin "2") (pinfunction "2_2") (pintype "unspecified"))
      (node (ref "R-4-1V-INDICATOR") (pin "1") (pinfunction "1_1") (pintype "input"))
      (node (ref "R-4-2V-INDICATOR") (pin "1") (pinfunction "1_1") (pintype "input"))
      (node (ref "R-4-3V-INDICATOR") (pin "1") (pinfunction "1_1") (pintype "input"))
      (node (ref "R-4-5V-INDICATOR") (pin "1") (pinfunction "1_1") (pintype "input"))
      (node (ref "RESFORENAMEOUTINDICATOR1") (pin "1") (pinfunction "1_1") (pintype "input"))
      (node (ref "RESFORENAMEOUTINDICATOR2") (pin "1") (pinfunction "1_1") (pintype "input"))
      (node (ref "RESFORENAMEOUTINDICATOR3") (pin "1") (pinfunction "1_1") (pintype "input"))
      (node (ref "RESFORENAMEOUTINDICATOR4") (pin "1") (pinfunction "1_1") (pintype "input"))
      (node (ref "U11") (pin "1") (pinfunction "VCCA_1") (pintype "unspecified"))
      (node (ref "U11") (pin "5") (pinfunction "EN_5") (pintype "unspecified"))
      (node (ref "U11") (pin "8") (pinfunction "VCCB_8") (pintype "unspecified"))
      (node (ref "U2") (pin "3") (pinfunction "Vin_3") (pintype "unspecified"))
      (node (ref "U6") (pin "14") (pinfunction "VCCB_14") (pintype "unspecified"))
      (node (ref "U8") (pin "14") (pinfunction "VCC_14") (pintype "unspecified"))
      (node (ref "USB1") (pin "1") (pinfunction "VBUS_1") (pintype "unspecified"))
      (node (ref "USB2") (pin "1") (pinfunction "VBUS_1") (pintype "unspecified"))
    )
    (net (code "3") (name "12V") (class "Default")
      (node (ref "CAP-2-ANALOG-REF") (pin "1") (pinfunction "1_1") (pintype "unspecified"))
      (node (ref "CN4") (pin "2") (pinfunction "2_2") (pintype "unspecified"))
      (node (ref "H4") (pin "3") (pinfunction "3_3") (pintype "unspecified"))
      (node (ref "R-4-12V-INDICATOR") (pin "1") (pinfunction "1_1") (pintype "input"))
    )
    (net (code "4") (name "AREF") (class "Default")
      (node (ref "CAP-4-ANALOG-REF") (pin "1") (pinfunction "1_1") (pintype "unspecified"))
    )
    (net (code "5") (name "COIN") (class "Default")
      (node (ref "H4") (pin "2") (pinfunction "2_2") (pintype "unspecified"))
    )
    (net (code "6") (name "DISP-SCL") (class "Default")
      (node (ref "H3") (pin "4") (pinfunction "4_4") (pintype "unspecified"))
      (node (ref "R5") (pin "1") (pinfunction "1_1") (pintype "input"))
    )
    (net (code "7") (name "DISP-SDA") (class "Default")
      (node (ref "H3") (pin "3") (pinfunction "3_3") (pintype "unspecified"))
      (node (ref "R6") (pin "1") (pinfunction "1_1") (pintype "input"))
    )
    (net (code "8") (name "ENABLE-OUT") (class "Default")
      (node (ref "U12") (pin "5") (pinfunction "5B_5") (pintype "unspecified"))
    )
    (net (code "9") (name "GND") (class "Default")
      (node (ref "12V-INDICATOR") (pin "1") (pinfunction "-_1") (pintype "unspecified"))
      (node (ref "5V-INDICATOR") (pin "1") (pinfunction "-_1") (pintype "unspecified"))
      (node (ref "C17") (pin "2") (pinfunction "2_2") (pintype "unspecified"))
      (node (ref "C5") (pin "2") (pinfunction "2_2") (pintype "unspecified"))
      (node (ref "C6") (pin "2") (pinfunction "2_2") (pintype "unspecified"))
      (node (ref "CAP-1-ANALOG-REF") (pin "2") (pinfunction "2_2") (pintype "unspecified"))
      (node (ref "CAP-2-ANALOG-REF") (pin "2") (pinfunction "2_2") (pintype "unspecified"))
      (node (ref "CAP-4-ANALOG-REF") (pin "2") (pinfunction "2_2") (pintype "unspecified"))
      (node (ref "CAP1-FOR-3.3V-PS") (pin "2") (pinfunction "2_2") (pintype "input"))
      (node (ref "CAP2-FOR-3.3V-PS") (pin "2") (pinfunction "2_2") (pintype "input"))
      (node (ref "CARD1") (pin "10") (pinfunction "G3_10") (pintype "input"))
      (node (ref "CARD1") (pin "11") (pinfunction "G4_11") (pintype "input"))
      (node (ref "CARD1") (pin "12") (pinfunction "G1_12") (pintype "input"))
      (node (ref "CARD1") (pin "13") (pinfunction "G2_13") (pintype "input"))
      (node (ref "CARD1") (pin "6") (pinfunction "VSS_6") (pintype "input"))
      (node (ref "CN3") (pin "2") (pinfunction "2_2") (pintype "unspecified"))
      (node (ref "CN4") (pin "1") (pinfunction "1_1") (pintype "unspecified"))
      (node (ref "CRYSTAL-CAP-1") (pin "1") (pinfunction "1_1") (pintype "input"))
      (node (ref "CRYSTAL-CAP-2") (pin "1") (pinfunction "1_1") (pintype "input"))
      (node (ref "H3") (pin "1") (pinfunction "1_1") (pintype "unspecified"))
      (node (ref "H4") (pin "1") (pinfunction "1_1") (pintype "unspecified"))
      (node (ref "U11") (pin "4") (pinfunction "GND_4") (pintype "unspecified"))
      (node (ref "U12") (pin "8") (pinfunction "E_8") (pintype "unspecified"))
      (node (ref "U2") (pin "1") (pinfunction "GND/ADJ_1") (pintype "unspecified"))
      (node (ref "U6") (pin "7") (pinfunction "GND_7") (pintype "unspecified"))
      (node (ref "U8") (pin "7") (pinfunction "GND_7") (pintype "unspecified"))
      (node (ref "USB1") (pin "5") (pinfunction "GND_5") (pintype "unspecified"))
      (node (ref "USB1") (pin "6") (pinfunction "6_6") (pintype "unspecified"))
      (node (ref "USB2") (pin "6") (pinfunction "6_6") (pintype "unspecified"))
      (node (ref "X2") (pin "2") (pinfunction "GND_2") (pintype "unspecified"))
      (node (ref "X2") (pin "4") (pinfunction "GND_4") (pintype "unspecified"))
    )
    (net (code "10") (name "ICSP-MISO") (class "Default")
      (node (ref "U6") (pin "13") (pinfunction "B1_13") (pintype "unspecified"))
      (node (ref "USB2") (pin "2") (pinfunction "D-_2") (pintype "unspecified"))
    )
    (net (code "11") (name "ICSP-MOSI") (class "Default")
      (node (ref "U6") (pin "11") (pinfunction "B3_11") (pintype "unspecified"))
      (node (ref "USB2") (pin "4") (pinfunction "ID_4") (pintype "unspecified"))
    )
    (net (code "12") (name "ICSP-RESET") (class "Default")
      (node (ref "U8") (pin "1") (pinfunction "1A_1") (pintype "unspecified"))
      (node (ref "USB2") (pin "5") (pinfunction "GND_5") (pintype "unspecified"))
    )
    (net (code "13") (name "ICSP-SCK") (class "Default")
      (node (ref "U6") (pin "12") (pinfunction "B2_12") (pintype "unspecified"))
      (node (ref "USB2") (pin "3") (pinfunction "D+_3") (pintype "unspecified"))
    )
    (net (code "14") (name "INP-ACTIVITY") (class "Default")
      (node (ref "U8") (pin "11") (pinfunction "5A_11") (pintype "unspecified"))
    )
    (net (code "15") (name "INV-INP-ACTIVITY") (class "Default")
      (node (ref "U12") (pin "1") (pinfunction "1B_1") (pintype "unspecified"))
      (node (ref "U8") (pin "10") (pinfunction "5Y_10") (pintype "unspecified"))
    )
    (net (code "16") (name "Net-(5V-INDICATOR-+)") (class "Default")
      (node (ref "5V-INDICATOR") (pin "2") (pinfunction "+_2") (pintype "unspecified"))
      (node (ref "R-4-5V-INDICATOR") (pin "2") (pinfunction "2_2") (pintype "input"))
    )
    (net (code "17") (name "Net-(12V-INDICATOR-+)") (class "Default")
      (node (ref "12V-INDICATOR") (pin "2") (pinfunction "+_2") (pintype "unspecified"))
      (node (ref "R-4-12V-INDICATOR") (pin "2") (pinfunction "2_2") (pintype "input"))
    )
    (net (code "18") (name "Net-(ENAMEOUTINDICATOR1-+)") (class "Default")
      (node (ref "ENAMEOUTINDICATOR1") (pin "2") (pinfunction "+_2") (pintype "unspecified"))
      (node (ref "RESFORENAMEOUTINDICATOR1") (pin "2") (pinfunction "2_2") (pintype "input"))
    )
    (net (code "19") (name "Net-(ENAMEOUTINDICATOR1--)") (class "Default")
      (node (ref "ENAMEOUTINDICATOR1") (pin "1") (pinfunction "-_1") (pintype "unspecified"))
      (node (ref "U12") (pin "12") (pinfunction "5C_12") (pintype "unspecified"))
    )
    (net (code "20") (name "Net-(ENAMEOUTINDICATOR2-+)") (class "Default")
      (node (ref "ENAMEOUTINDICATOR2") (pin "2") (pinfunction "+_2") (pintype "unspecified"))
      (node (ref "RESFORENAMEOUTINDICATOR2") (pin "2") (pinfunction "2_2") (pintype "input"))
    )
    (net (code "21") (name "Net-(ENAMEOUTINDICATOR3-+)") (class "Default")
      (node (ref "ENAMEOUTINDICATOR3") (pin "2") (pinfunction "+_2") (pintype "unspecified"))
      (node (ref "RESFORENAMEOUTINDICATOR3") (pin "2") (pinfunction "2_2") (pintype "input"))
    )
    (net (code "22") (name "Net-(ENAMEOUTINDICATOR4-+)") (class "Default")
      (node (ref "ENAMEOUTINDICATOR4") (pin "2") (pinfunction "+_2") (pintype "unspecified"))
      (node (ref "RESFORENAMEOUTINDICATOR4") (pin "2") (pinfunction "2_2") (pintype "input"))
    )
    (net (code "23") (name "Net-(INPUTACTIVITYINDICATOR1-+)") (class "Default")
      (node (ref "INPUTACTIVITYINDICATOR1") (pin "2") (pinfunction "+_2") (pintype "unspecified"))
      (node (ref "R-4-1V-INDICATOR") (pin "2") (pinfunction "2_2") (pintype "input"))
    )
    (net (code "24") (name "Net-(INPUTACTIVITYINDICATOR1--)") (class "Default")
      (node (ref "INPUTACTIVITYINDICATOR1") (pin "1") (pinfunction "-_1") (pintype "unspecified"))
      (node (ref "U12") (pin "16") (pinfunction "1C_16") (pintype "unspecified"))
    )
    (net (code "25") (name "Net-(INPUTACTIVITYINDICATOR2-+)") (class "Default")
      (node (ref "INPUTACTIVITYINDICATOR2") (pin "2") (pinfunction "+_2") (pintype "unspecified"))
      (node (ref "R-4-2V-INDICATOR") (pin "2") (pinfunction "2_2") (pintype "input"))
    )
    (net (code "26") (name "Net-(INPUTACTIVITYINDICATOR3-+)") (class "Default")
      (node (ref "INPUTACTIVITYINDICATOR3") (pin "2") (pinfunction "+_2") (pintype "unspecified"))
      (node (ref "R-4-3V-INDICATOR") (pin "2") (pinfunction "2_2") (pintype "input"))
    )
    (net (code "27") (name "Net-(U11-SCLA)") (class "Default")
      (node (ref "R5") (pin "2") (pinfunction "2_2") (pintype "input"))
      (node (ref "U11") (pin "2") (pinfunction "SCLA_2") (pintype "unspecified"))
    )
    (net (code "28") (name "Net-(U11-SDAA)") (class "Default")
      (node (ref "R6") (pin "2") (pinfunction "2_2") (pintype "input"))
      (node (ref "U11") (pin "3") (pinfunction "SDAA_3") (pintype "unspecified"))
    )
    (net (code "29") (name "OPP-RESET") (class "Default")
      (node (ref "U6") (pin "10") (pinfunction "B4_10") (pintype "unspecified"))
      (node (ref "U8") (pin "2") (pinfunction "1Y_2") (pintype "unspecified"))
    )
    (net (code "30") (name "SCL") (class "Default")
      (node (ref "U11") (pin "7") (pinfunction "SCLB_7") (pintype "unspecified"))
    )
    (net (code "31") (name "SD-PIN-2") (class "Default")
      (node (ref "CARD1") (pin "2") (pinfunction "CD/DAT3_2") (pintype "input"))
      (node (ref "U6") (pin "5") (pinfunction "A4_5") (pintype "unspecified"))
    )
    (net (code "32") (name "SD-PIN-3") (class "Default")
      (node (ref "CARD1") (pin "3") (pinfunction "CMD_3") (pintype "input"))
      (node (ref "U6") (pin "4") (pinfunction "A3_4") (pintype "unspecified"))
    )
    (net (code "33") (name "SD-PIN-5") (class "Default")
      (node (ref "CARD1") (pin "5") (pinfunction "CLK_5") (pintype "input"))
      (node (ref "U6") (pin "3") (pinfunction "A2_3") (pintype "unspecified"))
    )
    (net (code "34") (name "SD-PIN-7") (class "Default")
      (node (ref "CARD1") (pin "7") (pinfunction "DAT0_7") (pintype "input"))
      (node (ref "U6") (pin "2") (pinfunction "A1_2") (pintype "unspecified"))
    )
    (net (code "35") (name "SDA") (class "Default")
      (node (ref "U11") (pin "6") (pinfunction "SDAB_6") (pintype "unspecified"))
    )
    (net (code "36") (name "XTAL1") (class "Default")
      (node (ref "CRYSTAL-CAP-1") (pin "2") (pinfunction "2_2") (pintype "input"))
      (node (ref "X2") (pin "3") (pinfunction "OSC2_3") (pintype "unspecified"))
    )
    (net (code "37") (name "XTAL2") (class "Default")
      (node (ref "CRYSTAL-CAP-2") (pin "2") (pinfunction "2_2") (pintype "input"))
      (node (ref "X2") (pin "1") (pinfunction "OSC1_1") (pintype "unspecified"))
    )
    (net (code "38") (name "unconnected-(CARD1-CD-Pad9)") (class "Default")
      (node (ref "CARD1") (pin "9") (pinfunction "CD_9") (pintype "input+no_connect"))
    )
    (net (code "39") (name "unconnected-(CARD1-DAT1-Pad8)") (class "Default")
      (node (ref "CARD1") (pin "8") (pinfunction "DAT1_8") (pintype "input+no_connect"))
    )
    (net (code "40") (name "unconnected-(CARD1-DAT2-Pad1)") (class "Default")
      (node (ref "CARD1") (pin "1") (pinfunction "DAT2_1") (pintype "input+no_connect"))
    )
    (net (code "41") (name "unconnected-(CN1-Pad1)") (class "Default")
      (node (ref "CN1") (pin "1") (pinfunction "1_1") (pintype "unspecified"))
    )
    (net (code "42") (name "unconnected-(CN1-Pad2)") (class "Default")
      (node (ref "CN1") (pin "2") (pinfunction "2_2") (pintype "unspecified"))
    )
    (net (code "43") (name "unconnected-(CN1-Pad3)") (class "Default")
      (node (ref "CN1") (pin "3") (pinfunction "3_3") (pintype "unspecified"))
    )
    (net (code "44") (name "unconnected-(CN1-Pad4)") (class "Default")
      (node (ref "CN1") (pin "4") (pinfunction "4_4") (pintype "unspecified"))
    )
    (net (code "45") (name "unconnected-(CN1-Pad5)") (class "Default")
      (node (ref "CN1") (pin "5") (pinfunction "5_5") (pintype "unspecified"))
    )
    (net (code "46") (name "unconnected-(CN1-Pad6)") (class "Default")
      (node (ref "CN1") (pin "6") (pinfunction "6_6") (pintype "unspecified"))
    )
    (net (code "47") (name "unconnected-(CN1-Pad7)") (class "Default")
      (node (ref "CN1") (pin "7") (pinfunction "7_7") (pintype "unspecified"))
    )
    (net (code "48") (name "unconnected-(CN1-Pad8)") (class "Default")
      (node (ref "CN1") (pin "8") (pinfunction "8_8") (pintype "unspecified"))
    )
    (net (code "49") (name "unconnected-(CN1-Pad9)") (class "Default")
      (node (ref "CN1") (pin "9") (pinfunction "9_9") (pintype "unspecified"))
    )
    (net (code "50") (name "unconnected-(CN1-Pad10)") (class "Default")
      (node (ref "CN1") (pin "10") (pinfunction "10_10") (pintype "unspecified"))
    )
    (net (code "51") (name "unconnected-(CN1-Pad11)") (class "Default")
      (node (ref "CN1") (pin "11") (pinfunction "11_11") (pintype "unspecified"))
    )
    (net (code "52") (name "unconnected-(CN1-Pad12)") (class "Default")
      (node (ref "CN1") (pin "12") (pinfunction "12_12") (pintype "unspecified"))
    )
    (net (code "53") (name "unconnected-(CN1-Pad13)") (class "Default")
      (node (ref "CN1") (pin "13") (pinfunction "13_13") (pintype "unspecified"))
    )
    (net (code "54") (name "unconnected-(CN1-Pad14)") (class "Default")
      (node (ref "CN1") (pin "14") (pinfunction "14_14") (pintype "unspecified"))
    )
    (net (code "55") (name "unconnected-(CN1-Pad15)") (class "Default")
      (node (ref "CN1") (pin "15") (pinfunction "15_15") (pintype "unspecified"))
    )
    (net (code "56") (name "unconnected-(CN1-Pad16)") (class "Default")
      (node (ref "CN1") (pin "16") (pinfunction "16_16") (pintype "unspecified"))
    )
    (net (code "57") (name "unconnected-(CN2-Pad1)") (class "Default")
      (node (ref "CN2") (pin "1") (pinfunction "1_1") (pintype "unspecified"))
    )
    (net (code "58") (name "unconnected-(CN2-Pad2)") (class "Default")
      (node (ref "CN2") (pin "2") (pinfunction "2_2") (pintype "unspecified"))
    )
    (net (code "59") (name "unconnected-(CN2-Pad3)") (class "Default")
      (node (ref "CN2") (pin "3") (pinfunction "3_3") (pintype "unspecified"))
    )
    (net (code "60") (name "unconnected-(CN2-Pad4)") (class "Default")
      (node (ref "CN2") (pin "4") (pinfunction "4_4") (pintype "unspecified"))
    )
    (net (code "61") (name "unconnected-(CN2-Pad5)") (class "Default")
      (node (ref "CN2") (pin "5") (pinfunction "5_5") (pintype "unspecified"))
    )
    (net (code "62") (name "unconnected-(CN2-Pad6)") (class "Default")
      (node (ref "CN2") (pin "6") (pinfunction "6_6") (pintype "unspecified"))
    )
    (net (code "63") (name "unconnected-(CN2-Pad7)") (class "Default")
      (node (ref "CN2") (pin "7") (pinfunction "7_7") (pintype "unspecified"))
    )
    (net (code "64") (name "unconnected-(CN2-Pad8)") (class "Default")
      (node (ref "CN2") (pin "8") (pinfunction "8_8") (pintype "unspecified"))
    )
    (net (code "65") (name "unconnected-(CN2-Pad9)") (class "Default")
      (node (ref "CN2") (pin "9") (pinfunction "9_9") (pintype "unspecified"))
    )
    (net (code "66") (name "unconnected-(CN2-Pad10)") (class "Default")
      (node (ref "CN2") (pin "10") (pinfunction "10_10") (pintype "unspecified"))
    )
    (net (code "67") (name "unconnected-(CN2-Pad11)") (class "Default")
      (node (ref "CN2") (pin "11") (pinfunction "11_11") (pintype "unspecified"))
    )
    (net (code "68") (name "unconnected-(CN2-Pad12)") (class "Default")
      (node (ref "CN2") (pin "12") (pinfunction "12_12") (pintype "unspecified"))
    )
    (net (code "69") (name "unconnected-(CN2-Pad13)") (class "Default")
      (node (ref "CN2") (pin "13") (pinfunction "13_13") (pintype "unspecified"))
    )
    (net (code "70") (name "unconnected-(CN2-Pad14)") (class "Default")
      (node (ref "CN2") (pin "14") (pinfunction "14_14") (pintype "unspecified"))
    )
    (net (code "71") (name "unconnected-(CN2-Pad15)") (class "Default")
      (node (ref "CN2") (pin "15") (pinfunction "15_15") (pintype "unspecified"))
    )
    (net (code "72") (name "unconnected-(CN2-Pad16)") (class "Default")
      (node (ref "CN2") (pin "16") (pinfunction "16_16") (pintype "unspecified"))
    )
    (net (code "73") (name "unconnected-(ENAMEOUTINDICATOR2---Pad1)") (class "Default")
      (node (ref "ENAMEOUTINDICATOR2") (pin "1") (pinfunction "-_1") (pintype "unspecified"))
    )
    (net (code "74") (name "unconnected-(ENAMEOUTINDICATOR3---Pad1)") (class "Default")
      (node (ref "ENAMEOUTINDICATOR3") (pin "1") (pinfunction "-_1") (pintype "unspecified"))
    )
    (net (code "75") (name "unconnected-(ENAMEOUTINDICATOR4---Pad1)") (class "Default")
      (node (ref "ENAMEOUTINDICATOR4") (pin "1") (pinfunction "-_1") (pintype "unspecified"))
    )
    (net (code "76") (name "unconnected-(INPUTACTIVITYINDICATOR2---Pad1)") (class "Default")
      (node (ref "INPUTACTIVITYINDICATOR2") (pin "1") (pinfunction "-_1") (pintype "unspecified"))
    )
    (net (code "77") (name "unconnected-(INPUTACTIVITYINDICATOR3---Pad1)") (class "Default")
      (node (ref "INPUTACTIVITYINDICATOR3") (pin "1") (pinfunction "-_1") (pintype "unspecified"))
    )
    (net (code "78") (name "unconnected-(U1-AREF-Pad98)") (class "Default")
      (node (ref "U1") (pin "98") (pinfunction "AREF_98") (pintype "passive"))
    )
    (net (code "79") (name "unconnected-(U1-AVCC-Pad100)") (class "Default")
      (node (ref "U1") (pin "100") (pinfunction "AVCC_100") (pintype "passive"))
    )
    (net (code "80") (name "unconnected-(U1-GND-Pad11)") (class "Default")
      (node (ref "U1") (pin "11") (pinfunction "GND_11") (pintype "passive"))
    )
    (net (code "81") (name "unconnected-(U1-GND-Pad32)") (class "Default")
      (node (ref "U1") (pin "32") (pinfunction "GND_32") (pintype "passive"))
    )
    (net (code "82") (name "unconnected-(U1-GND-Pad62)") (class "Default")
      (node (ref "U1") (pin "62") (pinfunction "GND_62") (pintype "passive"))
    )
    (net (code "83") (name "unconnected-(U1-GND-Pad81)") (class "Default")
      (node (ref "U1") (pin "81") (pinfunction "GND_81") (pintype "passive"))
    )
    (net (code "84") (name "unconnected-(U1-GND-Pad99)") (class "Default")
      (node (ref "U1") (pin "99") (pinfunction "GND_99") (pintype "passive"))
    )
    (net (code "85") (name "unconnected-(U1-PA0_(AD0)-Pad78)") (class "Default")
      (node (ref "U1") (pin "78") (pinfunction "PA0_(AD0)_78") (pintype "bidirectional"))
    )
    (net (code "86") (name "unconnected-(U1-PA1_(AD1)-Pad77)") (class "Default")
      (node (ref "U1") (pin "77") (pinfunction "PA1_(AD1)_77") (pintype "bidirectional"))
    )
    (net (code "87") (name "unconnected-(U1-PA2_(AD2)-Pad76)") (class "Default")
      (node (ref "U1") (pin "76") (pinfunction "PA2_(AD2)_76") (pintype "bidirectional"))
    )
    (net (code "88") (name "unconnected-(U1-PA3_(AD3)-Pad75)") (class "Default")
      (node (ref "U1") (pin "75") (pinfunction "PA3_(AD3)_75") (pintype "bidirectional"))
    )
    (net (code "89") (name "unconnected-(U1-PA4_(AD4)-Pad74)") (class "Default")
      (node (ref "U1") (pin "74") (pinfunction "PA4_(AD4)_74") (pintype "bidirectional"))
    )
    (net (code "90") (name "unconnected-(U1-PA5_(AD5)-Pad73)") (class "Default")
      (node (ref "U1") (pin "73") (pinfunction "PA5_(AD5)_73") (pintype "bidirectional"))
    )
    (net (code "91") (name "unconnected-(U1-PA6_(AD6)-Pad72)") (class "Default")
      (node (ref "U1") (pin "72") (pinfunction "PA6_(AD6)_72") (pintype "bidirectional"))
    )
    (net (code "92") (name "unconnected-(U1-PA7_(AD7)-Pad71)") (class "Default")
      (node (ref "U1") (pin "71") (pinfunction "PA7_(AD7)_71") (pintype "bidirectional"))
    )
    (net (code "93") (name "unconnected-(U1-PB0_(SS#PCINT0)-Pad19)") (class "Default")
      (node (ref "U1") (pin "19") (pinfunction "PB0_(SS#PCINT0)_19") (pintype "bidirectional"))
    )
    (net (code "94") (name "unconnected-(U1-PB1_(SCKPCINT1)-Pad20)") (class "Default")
      (node (ref "U1") (pin "20") (pinfunction "PB1_(SCKPCINT1)_20") (pintype "bidirectional"))
    )
    (net (code "95") (name "unconnected-(U1-PB2_(MOSIPCINT2)-Pad21)") (class "Default")
      (node (ref "U1") (pin "21") (pinfunction "PB2_(MOSIPCINT2)_21") (pintype "bidirectional"))
    )
    (net (code "96") (name "unconnected-(U1-PB3_(MISOPCINT3)-Pad22)") (class "Default")
      (node (ref "U1") (pin "22") (pinfunction "PB3_(MISOPCINT3)_22") (pintype "bidirectional"))
    )
    (net (code "97") (name "unconnected-(U1-PB4_(OC2APCINT4)-Pad23)") (class "Default")
      (node (ref "U1") (pin "23") (pinfunction "PB4_(OC2APCINT4)_23") (pintype "bidirectional"))
    )
    (net (code "98") (name "unconnected-(U1-PB5_(OC1APCINT5)-Pad24)") (class "Default")
      (node (ref "U1") (pin "24") (pinfunction "PB5_(OC1APCINT5)_24") (pintype "bidirectional"))
    )
    (net (code "99") (name "unconnected-(U1-PB6_(OC1BPCINT6)-Pad25)") (class "Default")
      (node (ref "U1") (pin "25") (pinfunction "PB6_(OC1BPCINT6)_25") (pintype "bidirectional"))
    )
    (net (code "100") (name "unconnected-(U1-PB7_(OC0AOC1CPCINT7)-Pad26)") (class "Default")
      (node (ref "U1") (pin "26") (pinfunction "PB7_(OC0AOC1CPCINT7)_26") (pintype "bidirectional"))
    )
    (net (code "101") (name "unconnected-(U1-PC0_(A8)-Pad53)") (class "Default")
      (node (ref "U1") (pin "53") (pinfunction "PC0_(A8)_53") (pintype "bidirectional"))
    )
    (net (code "102") (name "unconnected-(U1-PC1_(A9)-Pad54)") (class "Default")
      (node (ref "U1") (pin "54") (pinfunction "PC1_(A9)_54") (pintype "bidirectional"))
    )
    (net (code "103") (name "unconnected-(U1-PC2_(A10)-Pad55)") (class "Default")
      (node (ref "U1") (pin "55") (pinfunction "PC2_(A10)_55") (pintype "bidirectional"))
    )
    (net (code "104") (name "unconnected-(U1-PC3_(A11)-Pad56)") (class "Default")
      (node (ref "U1") (pin "56") (pinfunction "PC3_(A11)_56") (pintype "bidirectional"))
    )
    (net (code "105") (name "unconnected-(U1-PC4_(A12)-Pad57)") (class "Default")
      (node (ref "U1") (pin "57") (pinfunction "PC4_(A12)_57") (pintype "bidirectional"))
    )
    (net (code "106") (name "unconnected-(U1-PC5_(A13)-Pad58)") (class "Default")
      (node (ref "U1") (pin "58") (pinfunction "PC5_(A13)_58") (pintype "bidirectional"))
    )
    (net (code "107") (name "unconnected-(U1-PC6_(A14)-Pad59)") (class "Default")
      (node (ref "U1") (pin "59") (pinfunction "PC6_(A14)_59") (pintype "bidirectional"))
    )
    (net (code "108") (name "unconnected-(U1-PC7_(A15)-Pad60)") (class "Default")
      (node (ref "U1") (pin "60") (pinfunction "PC7_(A15)_60") (pintype "bidirectional"))
    )
    (net (code "109") (name "unconnected-(U1-PD0_(SCLINT0)-Pad43)") (class "Default")
      (node (ref "U1") (pin "43") (pinfunction "PD0_(SCLINT0)_43") (pintype "bidirectional"))
    )
    (net (code "110") (name "unconnected-(U1-PD1_(SDAINT1)-Pad44)") (class "Default")
      (node (ref "U1") (pin "44") (pinfunction "PD1_(SDAINT1)_44") (pintype "bidirectional"))
    )
    (net (code "111") (name "unconnected-(U1-PD2_(RXD1INT2)-Pad45)") (class "Default")
      (node (ref "U1") (pin "45") (pinfunction "PD2_(RXD1INT2)_45") (pintype "bidirectional"))
    )
    (net (code "112") (name "unconnected-(U1-PD3_(TXD1INT3)-Pad46)") (class "Default")
      (node (ref "U1") (pin "46") (pinfunction "PD3_(TXD1INT3)_46") (pintype "bidirectional"))
    )
    (net (code "113") (name "unconnected-(U1-PD4_(ICP1)-Pad47)") (class "Default")
      (node (ref "U1") (pin "47") (pinfunction "PD4_(ICP1)_47") (pintype "bidirectional"))
    )
    (net (code "114") (name "unconnected-(U1-PD5_(XCK1)-Pad48)") (class "Default")
      (node (ref "U1") (pin "48") (pinfunction "PD5_(XCK1)_48") (pintype "bidirectional"))
    )
    (net (code "115") (name "unconnected-(U1-PD6_(T1)-Pad49)") (class "Default")
      (node (ref "U1") (pin "49") (pinfunction "PD6_(T1)_49") (pintype "bidirectional"))
    )
    (net (code "116") (name "unconnected-(U1-PD7_(T0)-Pad50)") (class "Default")
      (node (ref "U1") (pin "50") (pinfunction "PD7_(T0)_50") (pintype "bidirectional"))
    )
    (net (code "117") (name "unconnected-(U1-PE0_(RXD0PCINT8)-Pad2)") (class "Default")
      (node (ref "U1") (pin "2") (pinfunction "PE0_(RXD0PCINT8)_2") (pintype "bidirectional"))
    )
    (net (code "118") (name "unconnected-(U1-PE1_(TXD0)-Pad3)") (class "Default")
      (node (ref "U1") (pin "3") (pinfunction "PE1_(TXD0)_3") (pintype "bidirectional"))
    )
    (net (code "119") (name "unconnected-(U1-PE2_(XCK0AIN0)-Pad4)") (class "Default")
      (node (ref "U1") (pin "4") (pinfunction "PE2_(XCK0AIN0)_4") (pintype "bidirectional"))
    )
    (net (code "120") (name "unconnected-(U1-PE3_(OC3AAIN1)-Pad5)") (class "Default")
      (node (ref "U1") (pin "5") (pinfunction "PE3_(OC3AAIN1)_5") (pintype "bidirectional"))
    )
    (net (code "121") (name "unconnected-(U1-PE4_(OC3BINT4)-Pad6)") (class "Default")
      (node (ref "U1") (pin "6") (pinfunction "PE4_(OC3BINT4)_6") (pintype "bidirectional"))
    )
    (net (code "122") (name "unconnected-(U1-PE5_(OC3CINT5)-Pad7)") (class "Default")
      (node (ref "U1") (pin "7") (pinfunction "PE5_(OC3CINT5)_7") (pintype "bidirectional"))
    )
    (net (code "123") (name "unconnected-(U1-PE6_(T3INT6)-Pad8)") (class "Default")
      (node (ref "U1") (pin "8") (pinfunction "PE6_(T3INT6)_8") (pintype "bidirectional"))
    )
    (net (code "124") (name "unconnected-(U1-PE7_(CLKOICP3INT7)-Pad9)") (class "Default")
      (node (ref "U1") (pin "9") (pinfunction "PE7_(CLKOICP3INT7)_9") (pintype "bidirectional"))
    )
    (net (code "125") (name "unconnected-(U1-PF0_(ADC0)-Pad97)") (class "Default")
      (node (ref "U1") (pin "97") (pinfunction "PF0_(ADC0)_97") (pintype "bidirectional"))
    )
    (net (code "126") (name "unconnected-(U1-PF1_(ADC1)-Pad96)") (class "Default")
      (node (ref "U1") (pin "96") (pinfunction "PF1_(ADC1)_96") (pintype "bidirectional"))
    )
    (net (code "127") (name "unconnected-(U1-PF2_(ADC2)-Pad95)") (class "Default")
      (node (ref "U1") (pin "95") (pinfunction "PF2_(ADC2)_95") (pintype "bidirectional"))
    )
    (net (code "128") (name "unconnected-(U1-PF3_(ADC3)-Pad94)") (class "Default")
      (node (ref "U1") (pin "94") (pinfunction "PF3_(ADC3)_94") (pintype "bidirectional"))
    )
    (net (code "129") (name "unconnected-(U1-PF4_(ADC4TCK)-Pad93)") (class "Default")
      (node (ref "U1") (pin "93") (pinfunction "PF4_(ADC4TCK)_93") (pintype "bidirectional"))
    )
    (net (code "130") (name "unconnected-(U1-PF5_(ADC5TMS)-Pad92)") (class "Default")
      (node (ref "U1") (pin "92") (pinfunction "PF5_(ADC5TMS)_92") (pintype "bidirectional"))
    )
    (net (code "131") (name "unconnected-(U1-PF6_(ADC6TDO)-Pad91)") (class "Default")
      (node (ref "U1") (pin "91") (pinfunction "PF6_(ADC6TDO)_91") (pintype "bidirectional"))
    )
    (net (code "132") (name "unconnected-(U1-PF7_(ADC7TDI)-Pad90)") (class "Default")
      (node (ref "U1") (pin "90") (pinfunction "PF7_(ADC7TDI)_90") (pintype "bidirectional"))
    )
    (net (code "133") (name "unconnected-(U1-PG0_(WR#)-Pad51)") (class "Default")
      (node (ref "U1") (pin "51") (pinfunction "PG0_(WR#)_51") (pintype "bidirectional"))
    )
    (net (code "134") (name "unconnected-(U1-PG1_(RD#)-Pad52)") (class "Default")
      (node (ref "U1") (pin "52") (pinfunction "PG1_(RD#)_52") (pintype "bidirectional"))
    )
    (net (code "135") (name "unconnected-(U1-PG2_(ALE)-Pad70)") (class "Default")
      (node (ref "U1") (pin "70") (pinfunction "PG2_(ALE)_70") (pintype "bidirectional"))
    )
    (net (code "136") (name "unconnected-(U1-PG3_(TOSC2)-Pad28)") (class "Default")
      (node (ref "U1") (pin "28") (pinfunction "PG3_(TOSC2)_28") (pintype "bidirectional"))
    )
    (net (code "137") (name "unconnected-(U1-PG4_(TOSC1)-Pad29)") (class "Default")
      (node (ref "U1") (pin "29") (pinfunction "PG4_(TOSC1)_29") (pintype "bidirectional"))
    )
    (net (code "138") (name "unconnected-(U1-PG5_(OC0B)-Pad1)") (class "Default")
      (node (ref "U1") (pin "1") (pinfunction "PG5_(OC0B)_1") (pintype "bidirectional"))
    )
    (net (code "139") (name "unconnected-(U1-PH0_(RXD2)-Pad12)") (class "Default")
      (node (ref "U1") (pin "12") (pinfunction "PH0_(RXD2)_12") (pintype "bidirectional"))
    )
    (net (code "140") (name "unconnected-(U1-PH1_(TXD2)-Pad13)") (class "Default")
      (node (ref "U1") (pin "13") (pinfunction "PH1_(TXD2)_13") (pintype "bidirectional"))
    )
    (net (code "141") (name "unconnected-(U1-PH2_(XCK2)-Pad14)") (class "Default")
      (node (ref "U1") (pin "14") (pinfunction "PH2_(XCK2)_14") (pintype "bidirectional"))
    )
    (net (code "142") (name "unconnected-(U1-PH3_(OC4A)-Pad15)") (class "Default")
      (node (ref "U1") (pin "15") (pinfunction "PH3_(OC4A)_15") (pintype "bidirectional"))
    )
    (net (code "143") (name "unconnected-(U1-PH4_(OC4B)-Pad16)") (class "Default")
      (node (ref "U1") (pin "16") (pinfunction "PH4_(OC4B)_16") (pintype "bidirectional"))
    )
    (net (code "144") (name "unconnected-(U1-PH5_(OC4C)-Pad17)") (class "Default")
      (node (ref "U1") (pin "17") (pinfunction "PH5_(OC4C)_17") (pintype "bidirectional"))
    )
    (net (code "145") (name "unconnected-(U1-PH6_(OC2B)-Pad18)") (class "Default")
      (node (ref "U1") (pin "18") (pinfunction "PH6_(OC2B)_18") (pintype "bidirectional"))
    )
    (net (code "146") (name "unconnected-(U1-PH7_(T4)-Pad27)") (class "Default")
      (node (ref "U1") (pin "27") (pinfunction "PH7_(T4)_27") (pintype "bidirectional"))
    )
    (net (code "147") (name "unconnected-(U1-PJ0_(RXD3PCINT9)-Pad63)") (class "Default")
      (node (ref "U1") (pin "63") (pinfunction "PJ0_(RXD3PCINT9)_63") (pintype "bidirectional"))
    )
    (net (code "148") (name "unconnected-(U1-PJ1_(TXD3PCINT10)-Pad64)") (class "Default")
      (node (ref "U1") (pin "64") (pinfunction "PJ1_(TXD3PCINT10)_64") (pintype "bidirectional"))
    )
    (net (code "149") (name "unconnected-(U1-PJ2_(XCK3PCINT11)-Pad65)") (class "Default")
      (node (ref "U1") (pin "65") (pinfunction "PJ2_(XCK3PCINT11)_65") (pintype "bidirectional"))
    )
    (net (code "150") (name "unconnected-(U1-PJ3_(PCINT12)-Pad66)") (class "Default")
      (node (ref "U1") (pin "66") (pinfunction "PJ3_(PCINT12)_66") (pintype "bidirectional"))
    )
    (net (code "151") (name "unconnected-(U1-PJ4_(PCINT13)-Pad67)") (class "Default")
      (node (ref "U1") (pin "67") (pinfunction "PJ4_(PCINT13)_67") (pintype "bidirectional"))
    )
    (net (code "152") (name "unconnected-(U1-PJ5_(PCINT14)-Pad68)") (class "Default")
      (node (ref "U1") (pin "68") (pinfunction "PJ5_(PCINT14)_68") (pintype "bidirectional"))
    )
    (net (code "153") (name "unconnected-(U1-PJ6_(PCINT15)-Pad69)") (class "Default")
      (node (ref "U1") (pin "69") (pinfunction "PJ6_(PCINT15)_69") (pintype "bidirectional"))
    )
    (net (code "154") (name "unconnected-(U1-PJ7-Pad79)") (class "Default")
      (node (ref "U1") (pin "79") (pinfunction "PJ7_79") (pintype "bidirectional"))
    )
    (net (code "155") (name "unconnected-(U1-PK0_(ADC8PCINT16)-Pad89)") (class "Default")
      (node (ref "U1") (pin "89") (pinfunction "PK0_(ADC8PCINT16)_89") (pintype "bidirectional"))
    )
    (net (code "156") (name "unconnected-(U1-PK1_(ADC9PCINT17)-Pad88)") (class "Default")
      (node (ref "U1") (pin "88") (pinfunction "PK1_(ADC9PCINT17)_88") (pintype "bidirectional"))
    )
    (net (code "157") (name "unconnected-(U1-PK2_(ADC10PCINT18)-Pad87)") (class "Default")
      (node (ref "U1") (pin "87") (pinfunction "PK2_(ADC10PCINT18)_87") (pintype "bidirectional"))
    )
    (net (code "158") (name "unconnected-(U1-PK3_(ADC11PCINT19)-Pad86)") (class "Default")
      (node (ref "U1") (pin "86") (pinfunction "PK3_(ADC11PCINT19)_86") (pintype "bidirectional"))
    )
    (net (code "159") (name "unconnected-(U1-PK4_(ADC12PCINT20)-Pad85)") (class "Default")
      (node (ref "U1") (pin "85") (pinfunction "PK4_(ADC12PCINT20)_85") (pintype "bidirectional"))
    )
    (net (code "160") (name "unconnected-(U1-PK5_(ADC13PCINT21)-Pad84)") (class "Default")
      (node (ref "U1") (pin "84") (pinfunction "PK5_(ADC13PCINT21)_84") (pintype "bidirectional"))
    )
    (net (code "161") (name "unconnected-(U1-PK6_(ADC14PCINT22)-Pad83)") (class "Default")
      (node (ref "U1") (pin "83") (pinfunction "PK6_(ADC14PCINT22)_83") (pintype "bidirectional"))
    )
    (net (code "162") (name "unconnected-(U1-PK7_(ADC15PCINT23)-Pad82)") (class "Default")
      (node (ref "U1") (pin "82") (pinfunction "PK7_(ADC15PCINT23)_82") (pintype "bidirectional"))
    )
    (net (code "163") (name "unconnected-(U1-PL0_(ICP4)-Pad35)") (class "Default")
      (node (ref "U1") (pin "35") (pinfunction "PL0_(ICP4)_35") (pintype "bidirectional"))
    )
    (net (code "164") (name "unconnected-(U1-PL1_(ICP5)-Pad36)") (class "Default")
      (node (ref "U1") (pin "36") (pinfunction "PL1_(ICP5)_36") (pintype "bidirectional"))
    )
    (net (code "165") (name "unconnected-(U1-PL2_(T5)-Pad37)") (class "Default")
      (node (ref "U1") (pin "37") (pinfunction "PL2_(T5)_37") (pintype "bidirectional"))
    )
    (net (code "166") (name "unconnected-(U1-PL3_(OC5A)-Pad38)") (class "Default")
      (node (ref "U1") (pin "38") (pinfunction "PL3_(OC5A)_38") (pintype "bidirectional"))
    )
    (net (code "167") (name "unconnected-(U1-PL4_(OC5B)-Pad39)") (class "Default")
      (node (ref "U1") (pin "39") (pinfunction "PL4_(OC5B)_39") (pintype "bidirectional"))
    )
    (net (code "168") (name "unconnected-(U1-PL5_(OC5C)-Pad40)") (class "Default")
      (node (ref "U1") (pin "40") (pinfunction "PL5_(OC5C)_40") (pintype "bidirectional"))
    )
    (net (code "169") (name "unconnected-(U1-PL6-Pad41)") (class "Default")
      (node (ref "U1") (pin "41") (pinfunction "PL6_41") (pintype "bidirectional"))
    )
    (net (code "170") (name "unconnected-(U1-PL7-Pad42)") (class "Default")
      (node (ref "U1") (pin "42") (pinfunction "PL7_42") (pintype "bidirectional"))
    )
    (net (code "171") (name "unconnected-(U1-RESET#-Pad30)") (class "Default")
      (node (ref "U1") (pin "30") (pinfunction "RESET#_30") (pintype "unspecified"))
    )
    (net (code "172") (name "unconnected-(U1-VCC-Pad10)") (class "Default")
      (node (ref "U1") (pin "10") (pinfunction "VCC_10") (pintype "passive"))
    )
    (net (code "173") (name "unconnected-(U1-VCC-Pad31)") (class "Default")
      (node (ref "U1") (pin "31") (pinfunction "VCC_31") (pintype "passive"))
    )
    (net (code "174") (name "unconnected-(U1-VCC-Pad61)") (class "Default")
      (node (ref "U1") (pin "61") (pinfunction "VCC_61") (pintype "passive"))
    )
    (net (code "175") (name "unconnected-(U1-VCC-Pad80)") (class "Default")
      (node (ref "U1") (pin "80") (pinfunction "VCC_80") (pintype "passive"))
    )
    (net (code "176") (name "unconnected-(U1-XTAL1-Pad34)") (class "Default")
      (node (ref "U1") (pin "34") (pinfunction "XTAL1_34") (pintype "unspecified"))
    )
    (net (code "177") (name "unconnected-(U1-XTAL2-Pad33)") (class "Default")
      (node (ref "U1") (pin "33") (pinfunction "XTAL2_33") (pintype "output"))
    )
    (net (code "178") (name "unconnected-(U6-NC-Pad6)") (class "Default")
      (node (ref "U6") (pin "6") (pinfunction "NC_6") (pintype "unspecified+no_connect"))
    )
    (net (code "179") (name "unconnected-(U6-NC-Pad9)") (class "Default")
      (node (ref "U6") (pin "9") (pinfunction "NC_9") (pintype "unspecified+no_connect"))
    )
    (net (code "180") (name "unconnected-(U8-2A-Pad3)") (class "Default")
      (node (ref "U8") (pin "3") (pinfunction "2A_3") (pintype "unspecified+no_connect"))
    )
    (net (code "181") (name "unconnected-(U8-2Y-Pad4)") (class "Default")
      (node (ref "U8") (pin "4") (pinfunction "2Y_4") (pintype "unspecified+no_connect"))
    )
    (net (code "182") (name "unconnected-(U8-3A-Pad5)") (class "Default")
      (node (ref "U8") (pin "5") (pinfunction "3A_5") (pintype "unspecified+no_connect"))
    )
    (net (code "183") (name "unconnected-(U8-3Y-Pad6)") (class "Default")
      (node (ref "U8") (pin "6") (pinfunction "3Y_6") (pintype "unspecified+no_connect"))
    )
    (net (code "184") (name "unconnected-(U8-4A-Pad9)") (class "Default")
      (node (ref "U8") (pin "9") (pinfunction "4A_9") (pintype "unspecified+no_connect"))
    )
    (net (code "185") (name "unconnected-(U8-4Y-Pad8)") (class "Default")
      (node (ref "U8") (pin "8") (pinfunction "4Y_8") (pintype "unspecified+no_connect"))
    )
    (net (code "186") (name "unconnected-(U8-6A-Pad13)") (class "Default")
      (node (ref "U8") (pin "13") (pinfunction "6A_13") (pintype "unspecified+no_connect"))
    )
    (net (code "187") (name "unconnected-(U8-6Y-Pad12)") (class "Default")
      (node (ref "U8") (pin "12") (pinfunction "6Y_12") (pintype "unspecified+no_connect"))
    )
    (net (code "188") (name "unconnected-(U12-2B-Pad2)") (class "Default")
      (node (ref "U12") (pin "2") (pinfunction "2B_2") (pintype "unspecified+no_connect"))
    )
    (net (code "189") (name "unconnected-(U12-2C-Pad15)") (class "Default")
      (node (ref "U12") (pin "15") (pinfunction "2C_15") (pintype "unspecified+no_connect"))
    )
    (net (code "190") (name "unconnected-(U12-3B-Pad3)") (class "Default")
      (node (ref "U12") (pin "3") (pinfunction "3B_3") (pintype "unspecified+no_connect"))
    )
    (net (code "191") (name "unconnected-(U12-3C-Pad14)") (class "Default")
      (node (ref "U12") (pin "14") (pinfunction "3C_14") (pintype "unspecified+no_connect"))
    )
    (net (code "192") (name "unconnected-(U12-4B-Pad4)") (class "Default")
      (node (ref "U12") (pin "4") (pinfunction "4B_4") (pintype "unspecified+no_connect"))
    )
    (net (code "193") (name "unconnected-(U12-4C-Pad13)") (class "Default")
      (node (ref "U12") (pin "13") (pinfunction "4C_13") (pintype "unspecified+no_connect"))
    )
    (net (code "194") (name "unconnected-(U12-6B-Pad6)") (class "Default")
      (node (ref "U12") (pin "6") (pinfunction "6B_6") (pintype "unspecified+no_connect"))
    )
    (net (code "195") (name "unconnected-(U12-6C-Pad11)") (class "Default")
      (node (ref "U12") (pin "11") (pinfunction "6C_11") (pintype "unspecified+no_connect"))
    )
    (net (code "196") (name "unconnected-(U12-7B-Pad7)") (class "Default")
      (node (ref "U12") (pin "7") (pinfunction "7B_7") (pintype "unspecified+no_connect"))
    )
    (net (code "197") (name "unconnected-(U12-7C-Pad10)") (class "Default")
      (node (ref "U12") (pin "10") (pinfunction "7C_10") (pintype "unspecified+no_connect"))
    )
    (net (code "198") (name "unconnected-(U12-COM-Pad9)") (class "Default")
      (node (ref "U12") (pin "9") (pinfunction "COM_9") (pintype "unspecified+no_connect"))
    )
    (net (code "199") (name "unconnected-(USB1-D+-Pad3)") (class "Default")
      (node (ref "USB1") (pin "3") (pinfunction "D+_3") (pintype "unspecified+no_connect"))
    )
    (net (code "200") (name "unconnected-(USB1-D--Pad2)") (class "Default")
      (node (ref "USB1") (pin "2") (pinfunction "D-_2") (pintype "unspecified+no_connect"))
    )
    (net (code "201") (name "unconnected-(USB1-ID-Pad4)") (class "Default")
      (node (ref "USB1") (pin "4") (pinfunction "ID_4") (pintype "unspecified+no_connect"))
    )
  )
)
